# Mosfet_cct.net
KiCad netlist of a schematic drawn in Altium Designer
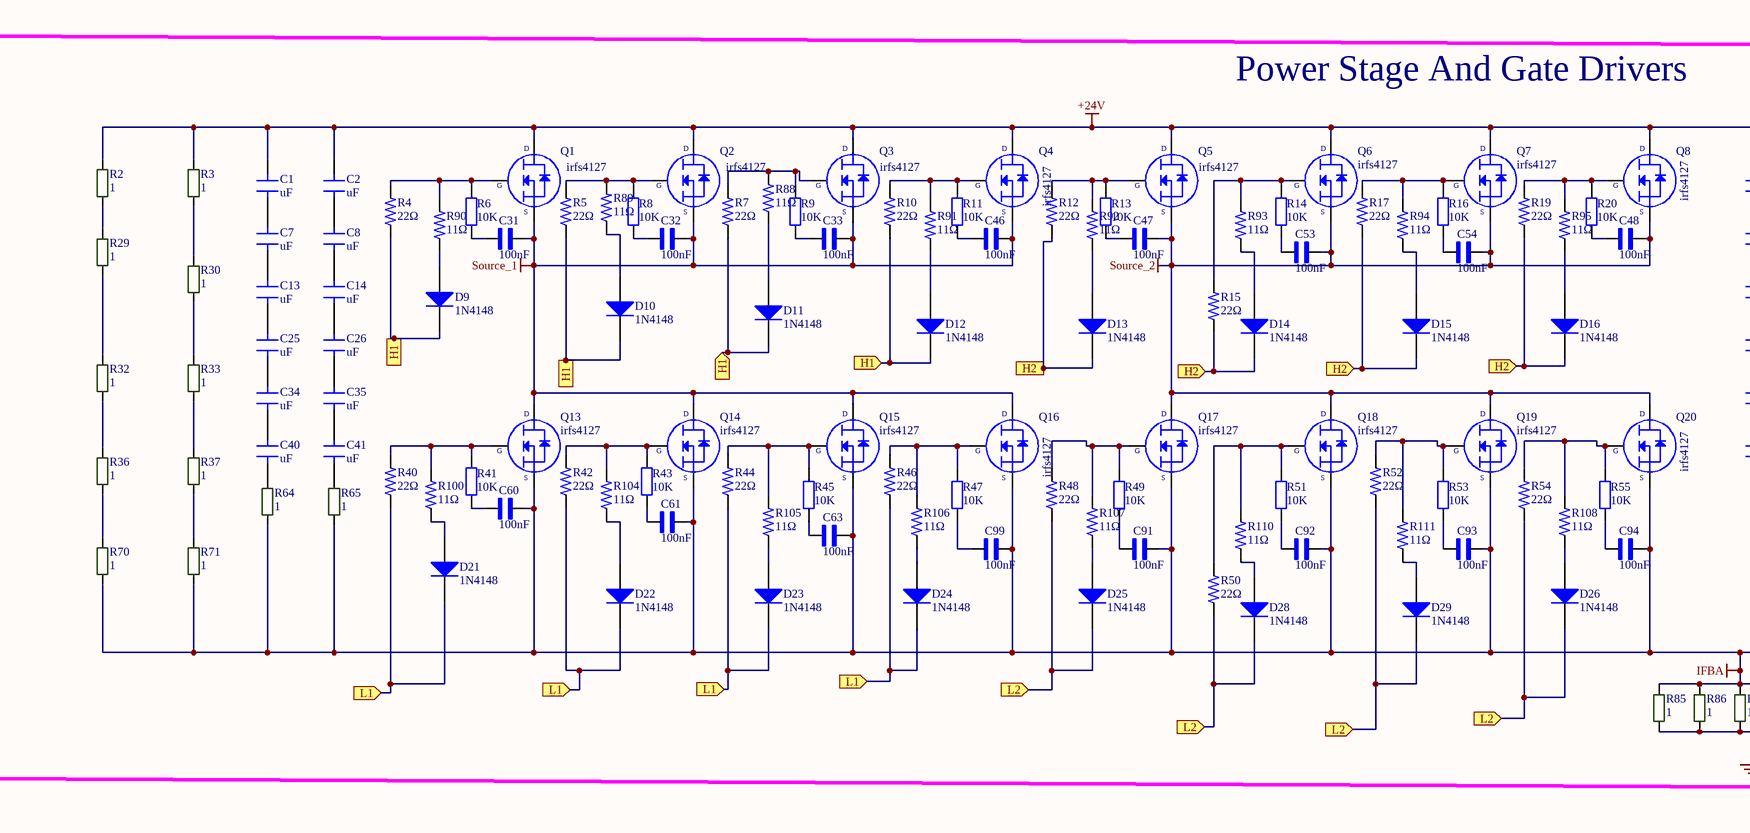
[diagram p0: Mosfet_cct.SchDoc, left]
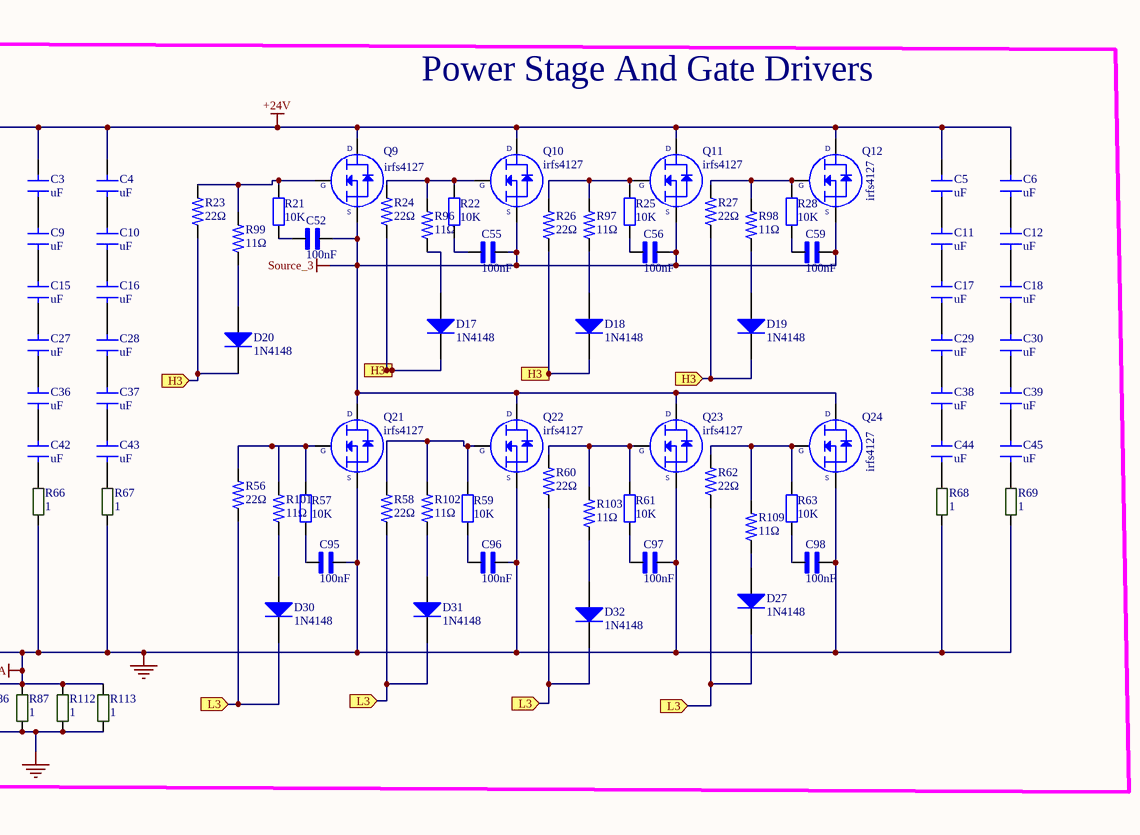
[diagram p1: Mosfet_cct.SchDoc, right]

(export (version "E")
  (design (tool "Eeschema 10.0.6"))
  (components
    (comp (ref "C1")
      (value "uF")
      (footprint "C-1206")
      (libsource (lib "LFI Power BoardSchlib1") (part "C-1206"))
    )
    (comp (ref "C2")
      (value "uF")
      (footprint "C-1206")
      (libsource (lib "LFI Power BoardSchlib1") (part "C-1206"))
    )
    (comp (ref "C3")
      (value "uF")
      (footprint "C-1206")
      (libsource (lib "LFI Power BoardSchlib1") (part "C-1206"))
    )
    (comp (ref "C4")
      (value "uF")
      (footprint "C-1206")
      (libsource (lib "LFI Power BoardSchlib1") (part "C-1206"))
    )
    (comp (ref "C5")
      (value "uF")
      (footprint "C-1206")
      (libsource (lib "LFI Power BoardSchlib1") (part "C-1206"))
    )
    (comp (ref "C6")
      (value "uF")
      (footprint "C-1206")
      (libsource (lib "LFI Power BoardSchlib1") (part "C-1206"))
    )
    (comp (ref "C7")
      (value "uF")
      (footprint "C-1206")
      (libsource (lib "LFI Power BoardSchlib1") (part "C-1206"))
    )
    (comp (ref "C8")
      (value "uF")
      (footprint "C-1206")
      (libsource (lib "LFI Power BoardSchlib1") (part "C-1206"))
    )
    (comp (ref "C9")
      (value "uF")
      (footprint "C-1206")
      (libsource (lib "LFI Power BoardSchlib1") (part "C-1206"))
    )
    (comp (ref "C10")
      (value "uF")
      (footprint "C-1206")
      (libsource (lib "LFI Power BoardSchlib1") (part "C-1206"))
    )
    (comp (ref "C11")
      (value "uF")
      (footprint "C-1206")
      (libsource (lib "LFI Power BoardSchlib1") (part "C-1206"))
    )
    (comp (ref "C12")
      (value "uF")
      (footprint "C-1206")
      (libsource (lib "LFI Power BoardSchlib1") (part "C-1206"))
    )
    (comp (ref "C13")
      (value "uF")
      (footprint "C-1206")
      (libsource (lib "LFI Power BoardSchlib1") (part "C-1206"))
    )
    (comp (ref "C14")
      (value "uF")
      (footprint "C-1206")
      (libsource (lib "LFI Power BoardSchlib1") (part "C-1206"))
    )
    (comp (ref "C15")
      (value "uF")
      (footprint "C-1206")
      (libsource (lib "LFI Power BoardSchlib1") (part "C-1206"))
    )
    (comp (ref "C16")
      (value "uF")
      (footprint "C-1206")
      (libsource (lib "LFI Power BoardSchlib1") (part "C-1206"))
    )
    (comp (ref "C17")
      (value "uF")
      (footprint "C-1206")
      (libsource (lib "LFI Power BoardSchlib1") (part "C-1206"))
    )
    (comp (ref "C18")
      (value "uF")
      (footprint "C-1206")
      (libsource (lib "LFI Power BoardSchlib1") (part "C-1206"))
    )
    (comp (ref "C25")
      (value "uF")
      (footprint "C-1206")
      (libsource (lib "LFI Power BoardSchlib1") (part "C-1206"))
    )
    (comp (ref "C26")
      (value "uF")
      (footprint "C-1206")
      (libsource (lib "LFI Power BoardSchlib1") (part "C-1206"))
    )
    (comp (ref "C27")
      (value "uF")
      (footprint "C-1206")
      (libsource (lib "LFI Power BoardSchlib1") (part "C-1206"))
    )
    (comp (ref "C28")
      (value "uF")
      (footprint "C-1206")
      (libsource (lib "LFI Power BoardSchlib1") (part "C-1206"))
    )
    (comp (ref "C29")
      (value "uF")
      (footprint "C-1206")
      (libsource (lib "LFI Power BoardSchlib1") (part "C-1206"))
    )
    (comp (ref "C30")
      (value "uF")
      (footprint "C-1206")
      (libsource (lib "LFI Power BoardSchlib1") (part "C-1206"))
    )
    (comp (ref "C31")
      (value "100nF")
      (footprint "C-0805W")
      (fields
        (field (name "MF") "Wurth Electronics Inc")
        (field (name "MP") "885012207098")
        (field (name "BUYPART") "https://www.snapeda.com/parts/885012207098/Wurth%20Electronics%20Inc/view-part/4217223/?ref=eda")
      )
      (libsource (lib "PROJE") (part "CAP 100nF 50V SMT 0805"))
    )
    (comp (ref "C32")
      (value "100nF")
      (footprint "C-0805W")
      (fields
        (field (name "MF") "Wurth Electronics Inc")
        (field (name "MP") "885012207098")
        (field (name "BUYPART") "https://www.snapeda.com/parts/885012207098/Wurth%20Electronics%20Inc/view-part/4217223/?ref=eda")
      )
      (libsource (lib "PROJE") (part "CAP 100nF 50V SMT 0805"))
    )
    (comp (ref "C33")
      (value "100nF")
      (footprint "C-0805W")
      (fields
        (field (name "MF") "Wurth Electronics Inc")
        (field (name "MP") "885012207098")
        (field (name "BUYPART") "https://www.snapeda.com/parts/885012207098/Wurth%20Electronics%20Inc/view-part/4217223/?ref=eda")
      )
      (libsource (lib "PROJE") (part "CAP 100nF 50V SMT 0805"))
    )
    (comp (ref "C34")
      (value "uF")
      (footprint "C-1206")
      (libsource (lib "LFI Power BoardSchlib1") (part "C-1206"))
    )
    (comp (ref "C35")
      (value "uF")
      (footprint "C-1206")
      (libsource (lib "LFI Power BoardSchlib1") (part "C-1206"))
    )
    (comp (ref "C36")
      (value "uF")
      (footprint "C-1206")
      (libsource (lib "LFI Power BoardSchlib1") (part "C-1206"))
    )
    (comp (ref "C37")
      (value "uF")
      (footprint "C-1206")
      (libsource (lib "LFI Power BoardSchlib1") (part "C-1206"))
    )
    (comp (ref "C38")
      (value "uF")
      (footprint "C-1206")
      (libsource (lib "LFI Power BoardSchlib1") (part "C-1206"))
    )
    (comp (ref "C39")
      (value "uF")
      (footprint "C-1206")
      (libsource (lib "LFI Power BoardSchlib1") (part "C-1206"))
    )
    (comp (ref "C40")
      (value "uF")
      (footprint "C-1206")
      (libsource (lib "LFI Power BoardSchlib1") (part "C-1206"))
    )
    (comp (ref "C41")
      (value "uF")
      (footprint "C-1206")
      (libsource (lib "LFI Power BoardSchlib1") (part "C-1206"))
    )
    (comp (ref "C42")
      (value "uF")
      (footprint "C-1206")
      (libsource (lib "LFI Power BoardSchlib1") (part "C-1206"))
    )
    (comp (ref "C43")
      (value "uF")
      (footprint "C-1206")
      (libsource (lib "LFI Power BoardSchlib1") (part "C-1206"))
    )
    (comp (ref "C44")
      (value "uF")
      (footprint "C-1206")
      (libsource (lib "LFI Power BoardSchlib1") (part "C-1206"))
    )
    (comp (ref "C45")
      (value "uF")
      (footprint "C-1206")
      (libsource (lib "LFI Power BoardSchlib1") (part "C-1206"))
    )
    (comp (ref "C46")
      (value "100nF")
      (footprint "C-0805W")
      (fields
        (field (name "MF") "Wurth Electronics Inc")
        (field (name "MP") "885012207098")
        (field (name "BUYPART") "https://www.snapeda.com/parts/885012207098/Wurth%20Electronics%20Inc/view-part/4217223/?ref=eda")
      )
      (libsource (lib "PROJE") (part "CAP 100nF 50V SMT 0805"))
    )
    (comp (ref "C47")
      (value "100nF")
      (footprint "C-0805W")
      (fields
        (field (name "MF") "Wurth Electronics Inc")
        (field (name "MP") "885012207098")
        (field (name "BUYPART") "https://www.snapeda.com/parts/885012207098/Wurth%20Electronics%20Inc/view-part/4217223/?ref=eda")
      )
      (libsource (lib "PROJE") (part "CAP 100nF 50V SMT 0805"))
    )
    (comp (ref "C48")
      (value "100nF")
      (footprint "C-0805W")
      (fields
        (field (name "MF") "Wurth Electronics Inc")
        (field (name "MP") "885012207098")
        (field (name "BUYPART") "https://www.snapeda.com/parts/885012207098/Wurth%20Electronics%20Inc/view-part/4217223/?ref=eda")
      )
      (libsource (lib "PROJE") (part "CAP 100nF 50V SMT 0805"))
    )
    (comp (ref "C52")
      (value "100nF")
      (footprint "C-0805W")
      (fields
        (field (name "MF") "Wurth Electronics Inc")
        (field (name "MP") "885012207098")
        (field (name "BUYPART") "https://www.snapeda.com/parts/885012207098/Wurth%20Electronics%20Inc/view-part/4217223/?ref=eda")
      )
      (libsource (lib "PROJE") (part "CAP 100nF 50V SMT 0805"))
    )
    (comp (ref "C53")
      (value "100nF")
      (footprint "C-0805W")
      (fields
        (field (name "MF") "Wurth Electronics Inc")
        (field (name "MP") "885012207098")
        (field (name "BUYPART") "https://www.snapeda.com/parts/885012207098/Wurth%20Electronics%20Inc/view-part/4217223/?ref=eda")
      )
      (libsource (lib "PROJE") (part "CAP 100nF 50V SMT 0805"))
    )
    (comp (ref "C54")
      (value "100nF")
      (footprint "C-0805W")
      (fields
        (field (name "MF") "Wurth Electronics Inc")
        (field (name "MP") "885012207098")
        (field (name "BUYPART") "https://www.snapeda.com/parts/885012207098/Wurth%20Electronics%20Inc/view-part/4217223/?ref=eda")
      )
      (libsource (lib "PROJE") (part "CAP 100nF 50V SMT 0805"))
    )
    (comp (ref "C55")
      (value "100nF")
      (footprint "C-0805W")
      (fields
        (field (name "MF") "Wurth Electronics Inc")
        (field (name "MP") "885012207098")
        (field (name "BUYPART") "https://www.snapeda.com/parts/885012207098/Wurth%20Electronics%20Inc/view-part/4217223/?ref=eda")
      )
      (libsource (lib "PROJE") (part "CAP 100nF 50V SMT 0805"))
    )
    (comp (ref "C56")
      (value "100nF")
      (footprint "C-0805W")
      (fields
        (field (name "MF") "Wurth Electronics Inc")
        (field (name "MP") "885012207098")
        (field (name "BUYPART") "https://www.snapeda.com/parts/885012207098/Wurth%20Electronics%20Inc/view-part/4217223/?ref=eda")
      )
      (libsource (lib "PROJE") (part "CAP 100nF 50V SMT 0805"))
    )
    (comp (ref "C59")
      (value "100nF")
      (footprint "C-0805W")
      (fields
        (field (name "MF") "Wurth Electronics Inc")
        (field (name "MP") "885012207098")
        (field (name "BUYPART") "https://www.snapeda.com/parts/885012207098/Wurth%20Electronics%20Inc/view-part/4217223/?ref=eda")
      )
      (libsource (lib "PROJE") (part "CAP 100nF 50V SMT 0805"))
    )
    (comp (ref "C60")
      (value "100nF")
      (footprint "C-0805W")
      (fields
        (field (name "MF") "Wurth Electronics Inc")
        (field (name "MP") "885012207098")
        (field (name "BUYPART") "https://www.snapeda.com/parts/885012207098/Wurth%20Electronics%20Inc/view-part/4217223/?ref=eda")
      )
      (libsource (lib "PROJE") (part "CAP 100nF 50V SMT 0805"))
    )
    (comp (ref "C61")
      (value "100nF")
      (footprint "C-0805W")
      (fields
        (field (name "MF") "Wurth Electronics Inc")
        (field (name "MP") "885012207098")
        (field (name "BUYPART") "https://www.snapeda.com/parts/885012207098/Wurth%20Electronics%20Inc/view-part/4217223/?ref=eda")
      )
      (libsource (lib "PROJE") (part "CAP 100nF 50V SMT 0805"))
    )
    (comp (ref "C63")
      (value "100nF")
      (footprint "C-0805W")
      (fields
        (field (name "MF") "Wurth Electronics Inc")
        (field (name "MP") "885012207098")
        (field (name "BUYPART") "https://www.snapeda.com/parts/885012207098/Wurth%20Electronics%20Inc/view-part/4217223/?ref=eda")
      )
      (libsource (lib "PROJE") (part "CAP 100nF 50V SMT 0805"))
    )
    (comp (ref "C91")
      (value "100nF")
      (footprint "C-0805W")
      (fields
        (field (name "MF") "Wurth Electronics Inc")
        (field (name "MP") "885012207098")
        (field (name "BUYPART") "https://www.snapeda.com/parts/885012207098/Wurth%20Electronics%20Inc/view-part/4217223/?ref=eda")
      )
      (libsource (lib "PROJE") (part "CAP 100nF 50V SMT 0805"))
    )
    (comp (ref "C92")
      (value "100nF")
      (footprint "C-0805W")
      (fields
        (field (name "MF") "Wurth Electronics Inc")
        (field (name "MP") "885012207098")
        (field (name "BUYPART") "https://www.snapeda.com/parts/885012207098/Wurth%20Electronics%20Inc/view-part/4217223/?ref=eda")
      )
      (libsource (lib "PROJE") (part "CAP 100nF 50V SMT 0805"))
    )
    (comp (ref "C93")
      (value "100nF")
      (footprint "C-0805W")
      (fields
        (field (name "MF") "Wurth Electronics Inc")
        (field (name "MP") "885012207098")
        (field (name "BUYPART") "https://www.snapeda.com/parts/885012207098/Wurth%20Electronics%20Inc/view-part/4217223/?ref=eda")
      )
      (libsource (lib "PROJE") (part "CAP 100nF 50V SMT 0805"))
    )
    (comp (ref "C94")
      (value "100nF")
      (footprint "C-0805W")
      (fields
        (field (name "MF") "Wurth Electronics Inc")
        (field (name "MP") "885012207098")
        (field (name "BUYPART") "https://www.snapeda.com/parts/885012207098/Wurth%20Electronics%20Inc/view-part/4217223/?ref=eda")
      )
      (libsource (lib "PROJE") (part "CAP 100nF 50V SMT 0805"))
    )
    (comp (ref "C95")
      (value "100nF")
      (footprint "C-0805W")
      (fields
        (field (name "MF") "Wurth Electronics Inc")
        (field (name "MP") "885012207098")
        (field (name "BUYPART") "https://www.snapeda.com/parts/885012207098/Wurth%20Electronics%20Inc/view-part/4217223/?ref=eda")
      )
      (libsource (lib "PROJE") (part "CAP 100nF 50V SMT 0805"))
    )
    (comp (ref "C96")
      (value "100nF")
      (footprint "C-0805W")
      (fields
        (field (name "MF") "Wurth Electronics Inc")
        (field (name "MP") "885012207098")
        (field (name "BUYPART") "https://www.snapeda.com/parts/885012207098/Wurth%20Electronics%20Inc/view-part/4217223/?ref=eda")
      )
      (libsource (lib "PROJE") (part "CAP 100nF 50V SMT 0805"))
    )
    (comp (ref "C97")
      (value "100nF")
      (footprint "C-0805W")
      (fields
        (field (name "MF") "Wurth Electronics Inc")
        (field (name "MP") "885012207098")
        (field (name "BUYPART") "https://www.snapeda.com/parts/885012207098/Wurth%20Electronics%20Inc/view-part/4217223/?ref=eda")
      )
      (libsource (lib "PROJE") (part "CAP 100nF 50V SMT 0805"))
    )
    (comp (ref "C98")
      (value "100nF")
      (footprint "C-0805W")
      (fields
        (field (name "MF") "Wurth Electronics Inc")
        (field (name "MP") "885012207098")
        (field (name "BUYPART") "https://www.snapeda.com/parts/885012207098/Wurth%20Electronics%20Inc/view-part/4217223/?ref=eda")
      )
      (libsource (lib "PROJE") (part "CAP 100nF 50V SMT 0805"))
    )
    (comp (ref "C99")
      (value "100nF")
      (footprint "C-0805W")
      (fields
        (field (name "MF") "Wurth Electronics Inc")
        (field (name "MP") "885012207098")
        (field (name "BUYPART") "https://www.snapeda.com/parts/885012207098/Wurth%20Electronics%20Inc/view-part/4217223/?ref=eda")
      )
      (libsource (lib "PROJE") (part "CAP 100nF 50V SMT 0805"))
    )
    (comp (ref "D9")
      (value "1N4148 Diyot")
      (footprint "SOD-123")
      (description "DIODE GEN PURP 100V 150MA SOD123")
      (fields (field (name "DEGER") "1N4148"))
      (libsource (lib "PROJE") (part "1N4148"))
    )
    (comp (ref "D10")
      (value "1N4148 Diyot")
      (footprint "SOD-123")
      (description "DIODE GEN PURP 100V 150MA SOD123")
      (fields (field (name "DEGER") "1N4148"))
      (libsource (lib "PROJE") (part "1N4148"))
    )
    (comp (ref "D11")
      (value "1N4148 Diyot")
      (footprint "SOD-123")
      (description "DIODE GEN PURP 100V 150MA SOD123")
      (fields (field (name "DEGER") "1N4148"))
      (libsource (lib "PROJE") (part "1N4148"))
    )
    (comp (ref "D12")
      (value "1N4148 Diyot")
      (footprint "SOD-123")
      (description "DIODE GEN PURP 100V 150MA SOD123")
      (fields (field (name "DEGER") "1N4148"))
      (libsource (lib "PROJE") (part "1N4148"))
    )
    (comp (ref "D13")
      (value "1N4148 Diyot")
      (footprint "SOD-123")
      (description "DIODE GEN PURP 100V 150MA SOD123")
      (fields (field (name "DEGER") "1N4148"))
      (libsource (lib "PROJE") (part "1N4148"))
    )
    (comp (ref "D14")
      (value "1N4148 Diyot")
      (footprint "SOD-123")
      (description "DIODE GEN PURP 100V 150MA SOD123")
      (fields (field (name "DEGER") "1N4148"))
      (libsource (lib "PROJE") (part "1N4148"))
    )
    (comp (ref "D15")
      (value "1N4148 Diyot")
      (footprint "SOD-123")
      (description "DIODE GEN PURP 100V 150MA SOD123")
      (fields (field (name "DEGER") "1N4148"))
      (libsource (lib "PROJE") (part "1N4148"))
    )
    (comp (ref "D16")
      (value "1N4148 Diyot")
      (footprint "SOD-123")
      (description "DIODE GEN PURP 100V 150MA SOD123")
      (fields (field (name "DEGER") "1N4148"))
      (libsource (lib "PROJE") (part "1N4148"))
    )
    (comp (ref "D17")
      (value "1N4148 Diyot")
      (footprint "SOD-123")
      (description "DIODE GEN PURP 100V 150MA SOD123")
      (fields (field (name "DEGER") "1N4148"))
      (libsource (lib "PROJE") (part "1N4148"))
    )
    (comp (ref "D18")
      (value "1N4148 Diyot")
      (footprint "SOD-123")
      (description "DIODE GEN PURP 100V 150MA SOD123")
      (fields (field (name "DEGER") "1N4148"))
      (libsource (lib "PROJE") (part "1N4148"))
    )
    (comp (ref "D19")
      (value "1N4148 Diyot")
      (footprint "SOD-123")
      (description "DIODE GEN PURP 100V 150MA SOD123")
      (fields (field (name "DEGER") "1N4148"))
      (libsource (lib "PROJE") (part "1N4148"))
    )
    (comp (ref "D20")
      (value "1N4148 Diyot")
      (footprint "SOD-123")
      (description "DIODE GEN PURP 100V 150MA SOD123")
      (fields (field (name "DEGER") "1N4148"))
      (libsource (lib "PROJE") (part "1N4148"))
    )
    (comp (ref "D21")
      (value "1N4148 Diyot")
      (footprint "SOD-123")
      (description "DIODE GEN PURP 100V 150MA SOD123")
      (fields (field (name "DEGER") "1N4148"))
      (libsource (lib "PROJE") (part "1N4148"))
    )
    (comp (ref "D22")
      (value "1N4148 Diyot")
      (footprint "SOD-123")
      (description "DIODE GEN PURP 100V 150MA SOD123")
      (fields (field (name "DEGER") "1N4148"))
      (libsource (lib "PROJE") (part "1N4148"))
    )
    (comp (ref "D23")
      (value "1N4148 Diyot")
      (footprint "SOD-123")
      (description "DIODE GEN PURP 100V 150MA SOD123")
      (fields (field (name "DEGER") "1N4148"))
      (libsource (lib "PROJE") (part "1N4148"))
    )
    (comp (ref "D24")
      (value "1N4148 Diyot")
      (footprint "SOD-123")
      (description "DIODE GEN PURP 100V 150MA SOD123")
      (fields (field (name "DEGER") "1N4148"))
      (libsource (lib "PROJE") (part "1N4148"))
    )
    (comp (ref "D25")
      (value "1N4148 Diyot")
      (footprint "SOD-123")
      (description "DIODE GEN PURP 100V 150MA SOD123")
      (fields (field (name "DEGER") "1N4148"))
      (libsource (lib "PROJE") (part "1N4148"))
    )
    (comp (ref "D26")
      (value "1N4148 Diyot")
      (footprint "SOD-123")
      (description "DIODE GEN PURP 100V 150MA SOD123")
      (fields (field (name "DEGER") "1N4148"))
      (libsource (lib "PROJE") (part "1N4148"))
    )
    (comp (ref "D27")
      (value "1N4148 Diyot")
      (footprint "SOD-123")
      (description "DIODE GEN PURP 100V 150MA SOD123")
      (fields (field (name "DEGER") "1N4148"))
      (libsource (lib "PROJE") (part "1N4148"))
    )
    (comp (ref "D28")
      (value "1N4148 Diyot")
      (footprint "SOD-123")
      (description "DIODE GEN PURP 100V 150MA SOD123")
      (fields (field (name "DEGER") "1N4148"))
      (libsource (lib "PROJE") (part "1N4148"))
    )
    (comp (ref "D29")
      (value "1N4148 Diyot")
      (footprint "SOD-123")
      (description "DIODE GEN PURP 100V 150MA SOD123")
      (fields (field (name "DEGER") "1N4148"))
      (libsource (lib "PROJE") (part "1N4148"))
    )
    (comp (ref "D30")
      (value "1N4148 Diyot")
      (footprint "SOD-123")
      (description "DIODE GEN PURP 100V 150MA SOD123")
      (fields (field (name "DEGER") "1N4148"))
      (libsource (lib "PROJE") (part "1N4148"))
    )
    (comp (ref "D31")
      (value "1N4148 Diyot")
      (footprint "SOD-123")
      (description "DIODE GEN PURP 100V 150MA SOD123")
      (fields (field (name "DEGER") "1N4148"))
      (libsource (lib "PROJE") (part "1N4148"))
    )
    (comp (ref "D32")
      (value "1N4148 Diyot")
      (footprint "SOD-123")
      (description "DIODE GEN PURP 100V 150MA SOD123")
      (fields (field (name "DEGER") "1N4148"))
      (libsource (lib "PROJE") (part "1N4148"))
    )
    (comp (ref "Q1")
      (value "irfs4127")
      (footprint "DPAK_TO263")
      (description "MOSFET N-CH 200V 72A D2PAK")
      (fields
        (field (name "MANUFACTURER") "International Rectifier")
        (field (name "MANUFACTURER PART NUMBER") "IRFS4127TRLPBF")
      )
      (libsource (lib "LFI Power BoardSchlib1") (part "IRFS4127TRLPBF"))
    )
    (comp (ref "Q2")
      (value "irfs4127")
      (footprint "DPAK_TO263")
      (description "MOSFET N-CH 200V 72A D2PAK")
      (fields
        (field (name "MANUFACTURER") "International Rectifier")
        (field (name "MANUFACTURER PART NUMBER") "IRFS4127TRLPBF")
      )
      (libsource (lib "LFI Power BoardSchlib1") (part "IRFS4127TRLPBF"))
    )
    (comp (ref "Q3")
      (value "irfs4127")
      (footprint "DPAK_TO263")
      (description "MOSFET N-CH 200V 72A D2PAK")
      (fields
        (field (name "MANUFACTURER") "International Rectifier")
        (field (name "MANUFACTURER PART NUMBER") "IRFS4127TRLPBF")
      )
      (libsource (lib "LFI Power BoardSchlib1") (part "IRFS4127TRLPBF"))
    )
    (comp (ref "Q4")
      (value "irfs4127")
      (footprint "DPAK_TO263")
      (description "MOSFET N-CH 200V 72A D2PAK")
      (fields
        (field (name "MANUFACTURER") "International Rectifier")
        (field (name "MANUFACTURER PART NUMBER") "IRFS4127TRLPBF")
      )
      (libsource (lib "LFI Power BoardSchlib1") (part "IRFS4127TRLPBF"))
    )
    (comp (ref "Q5")
      (value "irfs4127")
      (footprint "DPAK_TO263")
      (description "MOSFET N-CH 200V 72A D2PAK")
      (fields
        (field (name "MANUFACTURER") "International Rectifier")
        (field (name "MANUFACTURER PART NUMBER") "IRFS4127TRLPBF")
      )
      (libsource (lib "LFI Power BoardSchlib1") (part "IRFS4127TRLPBF"))
    )
    (comp (ref "Q6")
      (value "irfs4127")
      (footprint "DPAK_TO263")
      (description "MOSFET N-CH 200V 72A D2PAK")
      (fields
        (field (name "MANUFACTURER") "International Rectifier")
        (field (name "MANUFACTURER PART NUMBER") "IRFS4127TRLPBF")
      )
      (libsource (lib "LFI Power BoardSchlib1") (part "IRFS4127TRLPBF"))
    )
    (comp (ref "Q7")
      (value "irfs4127")
      (footprint "DPAK_TO263")
      (description "MOSFET N-CH 200V 72A D2PAK")
      (fields
        (field (name "MANUFACTURER") "International Rectifier")
        (field (name "MANUFACTURER PART NUMBER") "IRFS4127TRLPBF")
      )
      (libsource (lib "LFI Power BoardSchlib1") (part "IRFS4127TRLPBF"))
    )
    (comp (ref "Q8")
      (value "irfs4127")
      (footprint "DPAK_TO263")
      (description "MOSFET N-CH 200V 72A D2PAK")
      (fields
        (field (name "MANUFACTURER") "International Rectifier")
        (field (name "MANUFACTURER PART NUMBER") "IRFS4127TRLPBF")
      )
      (libsource (lib "LFI Power BoardSchlib1") (part "IRFS4127TRLPBF"))
    )
    (comp (ref "Q9")
      (value "irfs4127")
      (footprint "DPAK_TO263")
      (description "MOSFET N-CH 200V 72A D2PAK")
      (fields
        (field (name "MANUFACTURER") "International Rectifier")
        (field (name "MANUFACTURER PART NUMBER") "IRFS4127TRLPBF")
      )
      (libsource (lib "LFI Power BoardSchlib1") (part "IRFS4127TRLPBF"))
    )
    (comp (ref "Q10")
      (value "irfs4127")
      (footprint "DPAK_TO263")
      (description "MOSFET N-CH 200V 72A D2PAK")
      (fields
        (field (name "MANUFACTURER") "International Rectifier")
        (field (name "MANUFACTURER PART NUMBER") "IRFS4127TRLPBF")
      )
      (libsource (lib "LFI Power BoardSchlib1") (part "IRFS4127TRLPBF"))
    )
    (comp (ref "Q11")
      (value "irfs4127")
      (footprint "DPAK_TO263")
      (description "MOSFET N-CH 200V 72A D2PAK")
      (fields
        (field (name "MANUFACTURER") "International Rectifier")
        (field (name "MANUFACTURER PART NUMBER") "IRFS4127TRLPBF")
      )
      (libsource (lib "LFI Power BoardSchlib1") (part "IRFS4127TRLPBF"))
    )
    (comp (ref "Q12")
      (value "irfs4127")
      (footprint "DPAK_TO263")
      (description "MOSFET N-CH 200V 72A D2PAK")
      (fields
        (field (name "MANUFACTURER") "International Rectifier")
        (field (name "MANUFACTURER PART NUMBER") "IRFS4127TRLPBF")
      )
      (libsource (lib "LFI Power BoardSchlib1") (part "IRFS4127TRLPBF"))
    )
    (comp (ref "Q13")
      (value "irfs4127")
      (footprint "DPAK_TO263")
      (description "MOSFET N-CH 200V 72A D2PAK")
      (fields
        (field (name "MANUFACTURER") "International Rectifier")
        (field (name "MANUFACTURER PART NUMBER") "IRFS4127TRLPBF")
      )
      (libsource (lib "LFI Power BoardSchlib1") (part "IRFS4127TRLPBF"))
    )
    (comp (ref "Q14")
      (value "irfs4127")
      (footprint "DPAK_TO263")
      (description "MOSFET N-CH 200V 72A D2PAK")
      (fields
        (field (name "MANUFACTURER") "International Rectifier")
        (field (name "MANUFACTURER PART NUMBER") "IRFS4127TRLPBF")
      )
      (libsource (lib "LFI Power BoardSchlib1") (part "IRFS4127TRLPBF"))
    )
    (comp (ref "Q15")
      (value "irfs4127")
      (footprint "DPAK_TO263")
      (description "MOSFET N-CH 200V 72A D2PAK")
      (fields
        (field (name "MANUFACTURER") "International Rectifier")
        (field (name "MANUFACTURER PART NUMBER") "IRFS4127TRLPBF")
      )
      (libsource (lib "LFI Power BoardSchlib1") (part "IRFS4127TRLPBF"))
    )
    (comp (ref "Q16")
      (value "irfs4127")
      (footprint "DPAK_TO263")
      (description "MOSFET N-CH 200V 72A D2PAK")
      (fields
        (field (name "MANUFACTURER") "International Rectifier")
        (field (name "MANUFACTURER PART NUMBER") "IRFS4127TRLPBF")
      )
      (libsource (lib "LFI Power BoardSchlib1") (part "IRFS4127TRLPBF"))
    )
    (comp (ref "Q17")
      (value "irfs4127")
      (footprint "DPAK_TO263")
      (description "MOSFET N-CH 200V 72A D2PAK")
      (fields
        (field (name "MANUFACTURER") "International Rectifier")
        (field (name "MANUFACTURER PART NUMBER") "IRFS4127TRLPBF")
      )
      (libsource (lib "LFI Power BoardSchlib1") (part "IRFS4127TRLPBF"))
    )
    (comp (ref "Q18")
      (value "irfs4127")
      (footprint "DPAK_TO263")
      (description "MOSFET N-CH 200V 72A D2PAK")
      (fields
        (field (name "MANUFACTURER") "International Rectifier")
        (field (name "MANUFACTURER PART NUMBER") "IRFS4127TRLPBF")
      )
      (libsource (lib "LFI Power BoardSchlib1") (part "IRFS4127TRLPBF"))
    )
    (comp (ref "Q19")
      (value "irfs4127")
      (footprint "DPAK_TO263")
      (description "MOSFET N-CH 200V 72A D2PAK")
      (fields
        (field (name "MANUFACTURER") "International Rectifier")
        (field (name "MANUFACTURER PART NUMBER") "IRFS4127TRLPBF")
      )
      (libsource (lib "LFI Power BoardSchlib1") (part "IRFS4127TRLPBF"))
    )
    (comp (ref "Q20")
      (value "irfs4127")
      (footprint "DPAK_TO263")
      (description "MOSFET N-CH 200V 72A D2PAK")
      (fields
        (field (name "MANUFACTURER") "International Rectifier")
        (field (name "MANUFACTURER PART NUMBER") "IRFS4127TRLPBF")
      )
      (libsource (lib "LFI Power BoardSchlib1") (part "IRFS4127TRLPBF"))
    )
    (comp (ref "Q21")
      (value "irfs4127")
      (footprint "DPAK_TO263")
      (description "MOSFET N-CH 200V 72A D2PAK")
      (fields
        (field (name "MANUFACTURER") "International Rectifier")
        (field (name "MANUFACTURER PART NUMBER") "IRFS4127TRLPBF")
      )
      (libsource (lib "LFI Power BoardSchlib1") (part "IRFS4127TRLPBF"))
    )
    (comp (ref "Q22")
      (value "irfs4127")
      (footprint "DPAK_TO263")
      (description "MOSFET N-CH 200V 72A D2PAK")
      (fields
        (field (name "MANUFACTURER") "International Rectifier")
        (field (name "MANUFACTURER PART NUMBER") "IRFS4127TRLPBF")
      )
      (libsource (lib "LFI Power BoardSchlib1") (part "IRFS4127TRLPBF"))
    )
    (comp (ref "Q23")
      (value "irfs4127")
      (footprint "DPAK_TO263")
      (description "MOSFET N-CH 200V 72A D2PAK")
      (fields
        (field (name "MANUFACTURER") "International Rectifier")
        (field (name "MANUFACTURER PART NUMBER") "IRFS4127TRLPBF")
      )
      (libsource (lib "LFI Power BoardSchlib1") (part "IRFS4127TRLPBF"))
    )
    (comp (ref "Q24")
      (value "irfs4127")
      (footprint "DPAK_TO263")
      (description "MOSFET N-CH 200V 72A D2PAK")
      (fields
        (field (name "MANUFACTURER") "International Rectifier")
        (field (name "MANUFACTURER PART NUMBER") "IRFS4127TRLPBF")
      )
      (libsource (lib "LFI Power BoardSchlib1") (part "IRFS4127TRLPBF"))
    )
    (comp (ref "R2")
      (value "1")
      (footprint "R-2512W")
      (libsource (lib "LFI Power BoardSchlib1") (part "0207 melf"))
    )
    (comp (ref "R3")
      (value "1")
      (footprint "R-2512W")
      (libsource (lib "LFI Power BoardSchlib1") (part "0207 melf"))
    )
    (comp (ref "R4")
      (value "22Ω")
      (footprint "R-1206W")
      (description "CRG1206 1% 22R")
      (fields (field (name "MP") "1623463-1"))
      (libsource (lib "PROJE") (part "RES 22Ω 1206"))
    )
    (comp (ref "R5")
      (value "22Ω")
      (footprint "R-1206W")
      (description "CRG1206 1% 22R")
      (fields (field (name "MP") "1623463-1"))
      (libsource (lib "PROJE") (part "RES 22Ω 1206"))
    )
    (comp (ref "R6")
      (value "RES SMD 10K OHM 1% 1/8W 0805")
      (footprint "R-0805W")
      (description "10 kOhms ±1% 0.125W, 1/8W Chip Resistor 0805 (2012 Metric) Moisture Resistant Thick Film")
      (fields (field (name "DEGER") "10K"))
      (libsource (lib "PROJE") (part "10K 0805"))
    )
    (comp (ref "R7")
      (value "22Ω")
      (footprint "R-1206W")
      (description "CRG1206 1% 22R")
      (fields (field (name "MP") "1623463-1"))
      (libsource (lib "PROJE") (part "RES 22Ω 1206"))
    )
    (comp (ref "R8")
      (value "RES SMD 10K OHM 1% 1/8W 0805")
      (footprint "R-0805W")
      (description "10 kOhms ±1% 0.125W, 1/8W Chip Resistor 0805 (2012 Metric) Moisture Resistant Thick Film")
      (fields (field (name "DEGER") "10K"))
      (libsource (lib "PROJE") (part "10K 0805"))
    )
    (comp (ref "R9")
      (value "RES SMD 10K OHM 1% 1/8W 0805")
      (footprint "R-0805W")
      (description "10 kOhms ±1% 0.125W, 1/8W Chip Resistor 0805 (2012 Metric) Moisture Resistant Thick Film")
      (fields (field (name "DEGER") "10K"))
      (libsource (lib "PROJE") (part "10K 0805"))
    )
    (comp (ref "R10")
      (value "22Ω")
      (footprint "R-1206W")
      (description "CRG1206 1% 22R")
      (fields (field (name "MP") "1623463-1"))
      (libsource (lib "PROJE") (part "RES 22Ω 1206"))
    )
    (comp (ref "R11")
      (value "RES SMD 10K OHM 1% 1/8W 0805")
      (footprint "R-0805W")
      (description "10 kOhms ±1% 0.125W, 1/8W Chip Resistor 0805 (2012 Metric) Moisture Resistant Thick Film")
      (fields (field (name "DEGER") "10K"))
      (libsource (lib "PROJE") (part "10K 0805"))
    )
    (comp (ref "R12")
      (value "22Ω")
      (footprint "R-1206W")
      (description "CRG1206 1% 22R")
      (fields (field (name "MP") "1623463-1"))
      (libsource (lib "PROJE") (part "RES 22Ω 1206"))
    )
    (comp (ref "R13")
      (value "RES SMD 10K OHM 1% 1/8W 0805")
      (footprint "R-0805W")
      (description "10 kOhms ±1% 0.125W, 1/8W Chip Resistor 0805 (2012 Metric) Moisture Resistant Thick Film")
      (fields (field (name "DEGER") "10K"))
      (libsource (lib "PROJE") (part "10K 0805"))
    )
    (comp (ref "R14")
      (value "RES SMD 10K OHM 1% 1/8W 0805")
      (footprint "R-0805W")
      (description "10 kOhms ±1% 0.125W, 1/8W Chip Resistor 0805 (2012 Metric) Moisture Resistant Thick Film")
      (fields (field (name "DEGER") "10K"))
      (libsource (lib "PROJE") (part "10K 0805"))
    )
    (comp (ref "R15")
      (value "22Ω")
      (footprint "R-1206W")
      (description "CRG1206 1% 22R")
      (fields (field (name "MP") "1623463-1"))
      (libsource (lib "PROJE") (part "RES 22Ω 1206"))
    )
    (comp (ref "R16")
      (value "RES SMD 10K OHM 1% 1/8W 0805")
      (footprint "R-0805W")
      (description "10 kOhms ±1% 0.125W, 1/8W Chip Resistor 0805 (2012 Metric) Moisture Resistant Thick Film")
      (fields (field (name "DEGER") "10K"))
      (libsource (lib "PROJE") (part "10K 0805"))
    )
    (comp (ref "R17")
      (value "22Ω")
      (footprint "R-1206W")
      (description "CRG1206 1% 22R")
      (fields (field (name "MP") "1623463-1"))
      (libsource (lib "PROJE") (part "RES 22Ω 1206"))
    )
    (comp (ref "R19")
      (value "22Ω")
      (footprint "R-1206W")
      (description "CRG1206 1% 22R")
      (fields (field (name "MP") "1623463-1"))
      (libsource (lib "PROJE") (part "RES 22Ω 1206"))
    )
    (comp (ref "R20")
      (value "RES SMD 10K OHM 1% 1/8W 0805")
      (footprint "R-0805W")
      (description "10 kOhms ±1% 0.125W, 1/8W Chip Resistor 0805 (2012 Metric) Moisture Resistant Thick Film")
      (fields (field (name "DEGER") "10K"))
      (libsource (lib "PROJE") (part "10K 0805"))
    )
    (comp (ref "R21")
      (value "RES SMD 10K OHM 1% 1/8W 0805")
      (footprint "R-0805W")
      (description "10 kOhms ±1% 0.125W, 1/8W Chip Resistor 0805 (2012 Metric) Moisture Resistant Thick Film")
      (fields (field (name "DEGER") "10K"))
      (libsource (lib "PROJE") (part "10K 0805"))
    )
    (comp (ref "R22")
      (value "RES SMD 10K OHM 1% 1/8W 0805")
      (footprint "R-0805W")
      (description "10 kOhms ±1% 0.125W, 1/8W Chip Resistor 0805 (2012 Metric) Moisture Resistant Thick Film")
      (fields (field (name "DEGER") "10K"))
      (libsource (lib "PROJE") (part "10K 0805"))
    )
    (comp (ref "R23")
      (value "22Ω")
      (footprint "R-1206W")
      (description "CRG1206 1% 22R")
      (fields (field (name "MP") "1623463-1"))
      (libsource (lib "PROJE") (part "RES 22Ω 1206"))
    )
    (comp (ref "R24")
      (value "22Ω")
      (footprint "R-1206W")
      (description "CRG1206 1% 22R")
      (fields (field (name "MP") "1623463-1"))
      (libsource (lib "PROJE") (part "RES 22Ω 1206"))
    )
    (comp (ref "R25")
      (value "RES SMD 10K OHM 1% 1/8W 0805")
      (footprint "R-0805W")
      (description "10 kOhms ±1% 0.125W, 1/8W Chip Resistor 0805 (2012 Metric) Moisture Resistant Thick Film")
      (fields (field (name "DEGER") "10K"))
      (libsource (lib "PROJE") (part "10K 0805"))
    )
    (comp (ref "R26")
      (value "22Ω")
      (footprint "R-1206W")
      (description "CRG1206 1% 22R")
      (fields (field (name "MP") "1623463-1"))
      (libsource (lib "PROJE") (part "RES 22Ω 1206"))
    )
    (comp (ref "R27")
      (value "22Ω")
      (footprint "R-1206W")
      (description "CRG1206 1% 22R")
      (fields (field (name "MP") "1623463-1"))
      (libsource (lib "PROJE") (part "RES 22Ω 1206"))
    )
    (comp (ref "R28")
      (value "RES SMD 10K OHM 1% 1/8W 0805")
      (footprint "R-0805W")
      (description "10 kOhms ±1% 0.125W, 1/8W Chip Resistor 0805 (2012 Metric) Moisture Resistant Thick Film")
      (fields (field (name "DEGER") "10K"))
      (libsource (lib "PROJE") (part "10K 0805"))
    )
    (comp (ref "R29")
      (value "1")
      (footprint "R-2512W")
      (libsource (lib "LFI Power BoardSchlib1") (part "0207 melf"))
    )
    (comp (ref "R30")
      (value "1")
      (footprint "R-2512W")
      (libsource (lib "LFI Power BoardSchlib1") (part "0207 melf"))
    )
    (comp (ref "R32")
      (value "1")
      (footprint "R-2512W")
      (libsource (lib "LFI Power BoardSchlib1") (part "0207 melf"))
    )
    (comp (ref "R33")
      (value "1")
      (footprint "R-2512W")
      (libsource (lib "LFI Power BoardSchlib1") (part "0207 melf"))
    )
    (comp (ref "R36")
      (value "1")
      (footprint "R-2512W")
      (libsource (lib "LFI Power BoardSchlib1") (part "0207 melf"))
    )
    (comp (ref "R37")
      (value "1")
      (footprint "R-2512W")
      (libsource (lib "LFI Power BoardSchlib1") (part "0207 melf"))
    )
    (comp (ref "R40")
      (value "22Ω")
      (footprint "R-1206W")
      (description "CRG1206 1% 22R")
      (fields (field (name "MP") "1623463-1"))
      (libsource (lib "PROJE") (part "RES 22Ω 1206"))
    )
    (comp (ref "R41")
      (value "RES SMD 10K OHM 1% 1/8W 0805")
      (footprint "R-0805W")
      (description "10 kOhms ±1% 0.125W, 1/8W Chip Resistor 0805 (2012 Metric) Moisture Resistant Thick Film")
      (fields (field (name "DEGER") "10K"))
      (libsource (lib "PROJE") (part "10K 0805"))
    )
    (comp (ref "R42")
      (value "22Ω")
      (footprint "R-1206W")
      (description "CRG1206 1% 22R")
      (fields (field (name "MP") "1623463-1"))
      (libsource (lib "PROJE") (part "RES 22Ω 1206"))
    )
    (comp (ref "R43")
      (value "RES SMD 10K OHM 1% 1/8W 0805")
      (footprint "R-0805W")
      (description "10 kOhms ±1% 0.125W, 1/8W Chip Resistor 0805 (2012 Metric) Moisture Resistant Thick Film")
      (fields (field (name "DEGER") "10K"))
      (libsource (lib "PROJE") (part "10K 0805"))
    )
    (comp (ref "R44")
      (value "22Ω")
      (footprint "R-1206W")
      (description "CRG1206 1% 22R")
      (fields (field (name "MP") "1623463-1"))
      (libsource (lib "PROJE") (part "RES 22Ω 1206"))
    )
    (comp (ref "R45")
      (value "RES SMD 10K OHM 1% 1/8W 0805")
      (footprint "R-0805W")
      (description "10 kOhms ±1% 0.125W, 1/8W Chip Resistor 0805 (2012 Metric) Moisture Resistant Thick Film")
      (fields (field (name "DEGER") "10K"))
      (libsource (lib "PROJE") (part "10K 0805"))
    )
    (comp (ref "R46")
      (value "22Ω")
      (footprint "R-1206W")
      (description "CRG1206 1% 22R")
      (fields (field (name "MP") "1623463-1"))
      (libsource (lib "PROJE") (part "RES 22Ω 1206"))
    )
    (comp (ref "R47")
      (value "RES SMD 10K OHM 1% 1/8W 0805")
      (footprint "R-0805W")
      (description "10 kOhms ±1% 0.125W, 1/8W Chip Resistor 0805 (2012 Metric) Moisture Resistant Thick Film")
      (fields (field (name "DEGER") "10K"))
      (libsource (lib "PROJE") (part "10K 0805"))
    )
    (comp (ref "R48")
      (value "22Ω")
      (footprint "R-1206W")
      (description "CRG1206 1% 22R")
      (fields (field (name "MP") "1623463-1"))
      (libsource (lib "PROJE") (part "RES 22Ω 1206"))
    )
    (comp (ref "R49")
      (value "RES SMD 10K OHM 1% 1/8W 0805")
      (footprint "R-0805W")
      (description "10 kOhms ±1% 0.125W, 1/8W Chip Resistor 0805 (2012 Metric) Moisture Resistant Thick Film")
      (fields (field (name "DEGER") "10K"))
      (libsource (lib "PROJE") (part "10K 0805"))
    )
    (comp (ref "R50")
      (value "22Ω")
      (footprint "R-1206W")
      (description "CRG1206 1% 22R")
      (fields (field (name "MP") "1623463-1"))
      (libsource (lib "PROJE") (part "RES 22Ω 1206"))
    )
    (comp (ref "R51")
      (value "RES SMD 10K OHM 1% 1/8W 0805")
      (footprint "R-0805W")
      (description "10 kOhms ±1% 0.125W, 1/8W Chip Resistor 0805 (2012 Metric) Moisture Resistant Thick Film")
      (fields (field (name "DEGER") "10K"))
      (libsource (lib "PROJE") (part "10K 0805"))
    )
    (comp (ref "R52")
      (value "22Ω")
      (footprint "R-1206W")
      (description "CRG1206 1% 22R")
      (fields (field (name "MP") "1623463-1"))
      (libsource (lib "PROJE") (part "RES 22Ω 1206"))
    )
    (comp (ref "R53")
      (value "RES SMD 10K OHM 1% 1/8W 0805")
      (footprint "R-0805W")
      (description "10 kOhms ±1% 0.125W, 1/8W Chip Resistor 0805 (2012 Metric) Moisture Resistant Thick Film")
      (fields (field (name "DEGER") "10K"))
      (libsource (lib "PROJE") (part "10K 0805"))
    )
    (comp (ref "R54")
      (value "22Ω")
      (footprint "R-1206W")
      (description "CRG1206 1% 22R")
      (fields (field (name "MP") "1623463-1"))
      (libsource (lib "PROJE") (part "RES 22Ω 1206"))
    )
    (comp (ref "R55")
      (value "RES SMD 10K OHM 1% 1/8W 0805")
      (footprint "R-0805W")
      (description "10 kOhms ±1% 0.125W, 1/8W Chip Resistor 0805 (2012 Metric) Moisture Resistant Thick Film")
      (fields (field (name "DEGER") "10K"))
      (libsource (lib "PROJE") (part "10K 0805"))
    )
    (comp (ref "R56")
      (value "22Ω")
      (footprint "R-1206W")
      (description "CRG1206 1% 22R")
      (fields (field (name "MP") "1623463-1"))
      (libsource (lib "PROJE") (part "RES 22Ω 1206"))
    )
    (comp (ref "R57")
      (value "RES SMD 10K OHM 1% 1/8W 0805")
      (footprint "R-0805W")
      (description "10 kOhms ±1% 0.125W, 1/8W Chip Resistor 0805 (2012 Metric) Moisture Resistant Thick Film")
      (fields (field (name "DEGER") "10K"))
      (libsource (lib "PROJE") (part "10K 0805"))
    )
    (comp (ref "R58")
      (value "22Ω")
      (footprint "R-1206W")
      (description "CRG1206 1% 22R")
      (fields (field (name "MP") "1623463-1"))
      (libsource (lib "PROJE") (part "RES 22Ω 1206"))
    )
    (comp (ref "R59")
      (value "RES SMD 10K OHM 1% 1/8W 0805")
      (footprint "R-0805W")
      (description "10 kOhms ±1% 0.125W, 1/8W Chip Resistor 0805 (2012 Metric) Moisture Resistant Thick Film")
      (fields (field (name "DEGER") "10K"))
      (libsource (lib "PROJE") (part "10K 0805"))
    )
    (comp (ref "R60")
      (value "22Ω")
      (footprint "R-1206W")
      (description "CRG1206 1% 22R")
      (fields (field (name "MP") "1623463-1"))
      (libsource (lib "PROJE") (part "RES 22Ω 1206"))
    )
    (comp (ref "R61")
      (value "RES SMD 10K OHM 1% 1/8W 0805")
      (footprint "R-0805W")
      (description "10 kOhms ±1% 0.125W, 1/8W Chip Resistor 0805 (2012 Metric) Moisture Resistant Thick Film")
      (fields (field (name "DEGER") "10K"))
      (libsource (lib "PROJE") (part "10K 0805"))
    )
    (comp (ref "R62")
      (value "22Ω")
      (footprint "R-1206W")
      (description "CRG1206 1% 22R")
      (fields (field (name "MP") "1623463-1"))
      (libsource (lib "PROJE") (part "RES 22Ω 1206"))
    )
    (comp (ref "R63")
      (value "RES SMD 10K OHM 1% 1/8W 0805")
      (footprint "R-0805W")
      (description "10 kOhms ±1% 0.125W, 1/8W Chip Resistor 0805 (2012 Metric) Moisture Resistant Thick Film")
      (fields (field (name "DEGER") "10K"))
      (libsource (lib "PROJE") (part "10K 0805"))
    )
    (comp (ref "R64")
      (value "1")
      (footprint "R-2512W")
      (libsource (lib "LFI Power BoardSchlib1") (part "0207 melf"))
    )
    (comp (ref "R65")
      (value "1")
      (footprint "R-2512W")
      (libsource (lib "LFI Power BoardSchlib1") (part "0207 melf"))
    )
    (comp (ref "R66")
      (value "1")
      (footprint "R-2512W")
      (libsource (lib "LFI Power BoardSchlib1") (part "0207 melf"))
    )
    (comp (ref "R67")
      (value "1")
      (footprint "R-2512W")
      (libsource (lib "LFI Power BoardSchlib1") (part "0207 melf"))
    )
    (comp (ref "R68")
      (value "1")
      (footprint "R-2512W")
      (libsource (lib "LFI Power BoardSchlib1") (part "0207 melf"))
    )
    (comp (ref "R69")
      (value "1")
      (footprint "R-2512W")
      (libsource (lib "LFI Power BoardSchlib1") (part "0207 melf"))
    )
    (comp (ref "R70")
      (value "1")
      (footprint "R-2512W")
      (libsource (lib "LFI Power BoardSchlib1") (part "0207 melf"))
    )
    (comp (ref "R71")
      (value "1")
      (footprint "R-2512W")
      (libsource (lib "LFI Power BoardSchlib1") (part "0207 melf"))
    )
    (comp (ref "R85")
      (value "1")
      (footprint "R-2512W")
      (libsource (lib "LFI Power BoardSchlib1") (part "0207 melf"))
    )
    (comp (ref "R86")
      (value "1")
      (footprint "R-2512W")
      (libsource (lib "LFI Power BoardSchlib1") (part "0207 melf"))
    )
    (comp (ref "R87")
      (value "1")
      (footprint "R-2512W")
      (libsource (lib "LFI Power BoardSchlib1") (part "0207 melf"))
    )
    (comp (ref "R88")
      (value "11Ω")
      (footprint "R-1206W")
      (description "CRG1206 1% 11R")
      (fields (field (name "MP") "1623463-1"))
      (libsource (lib "PROJE") (part "RES 11Ω 1206"))
    )
    (comp (ref "R89")
      (value "11Ω")
      (footprint "R-1206W")
      (description "CRG1206 1% 11R")
      (fields (field (name "MP") "1623463-1"))
      (libsource (lib "PROJE") (part "RES 11Ω 1206"))
    )
    (comp (ref "R90")
      (value "11Ω")
      (footprint "R-1206W")
      (description "CRG1206 1% 11R")
      (fields (field (name "MP") "1623463-1"))
      (libsource (lib "PROJE") (part "RES 11Ω 1206"))
    )
    (comp (ref "R91")
      (value "11Ω")
      (footprint "R-1206W")
      (description "CRG1206 1% 11R")
      (fields (field (name "MP") "1623463-1"))
      (libsource (lib "PROJE") (part "RES 11Ω 1206"))
    )
    (comp (ref "R92")
      (value "11Ω")
      (footprint "R-1206W")
      (description "CRG1206 1% 11R")
      (fields (field (name "MP") "1623463-1"))
      (libsource (lib "PROJE") (part "RES 11Ω 1206"))
    )
    (comp (ref "R93")
      (value "11Ω")
      (footprint "R-1206W")
      (description "CRG1206 1% 11R")
      (fields (field (name "MP") "1623463-1"))
      (libsource (lib "PROJE") (part "RES 11Ω 1206"))
    )
    (comp (ref "R94")
      (value "11Ω")
      (footprint "R-1206W")
      (description "CRG1206 1% 11R")
      (fields (field (name "MP") "1623463-1"))
      (libsource (lib "PROJE") (part "RES 11Ω 1206"))
    )
    (comp (ref "R95")
      (value "11Ω")
      (footprint "R-1206W")
      (description "CRG1206 1% 11R")
      (fields (field (name "MP") "1623463-1"))
      (libsource (lib "PROJE") (part "RES 11Ω 1206"))
    )
    (comp (ref "R96")
      (value "11Ω")
      (footprint "R-1206W")
      (description "CRG1206 1% 11R")
      (fields (field (name "MP") "1623463-1"))
      (libsource (lib "PROJE") (part "RES 11Ω 1206"))
    )
    (comp (ref "R97")
      (value "11Ω")
      (footprint "R-1206W")
      (description "CRG1206 1% 11R")
      (fields (field (name "MP") "1623463-1"))
      (libsource (lib "PROJE") (part "RES 11Ω 1206"))
    )
    (comp (ref "R98")
      (value "11Ω")
      (footprint "R-1206W")
      (description "CRG1206 1% 11R")
      (fields (field (name "MP") "1623463-1"))
      (libsource (lib "PROJE") (part "RES 11Ω 1206"))
    )
    (comp (ref "R99")
      (value "11Ω")
      (footprint "R-1206W")
      (description "CRG1206 1% 11R")
      (fields (field (name "MP") "1623463-1"))
      (libsource (lib "PROJE") (part "RES 11Ω 1206"))
    )
    (comp (ref "R100")
      (value "11Ω")
      (footprint "R-1206W")
      (description "CRG1206 1% 11R")
      (fields (field (name "MP") "1623463-1"))
      (libsource (lib "PROJE") (part "RES 11Ω 1206"))
    )
    (comp (ref "R101")
      (value "11Ω")
      (footprint "R-1206W")
      (description "CRG1206 1% 11R")
      (fields (field (name "MP") "1623463-1"))
      (libsource (lib "PROJE") (part "RES 11Ω 1206"))
    )
    (comp (ref "R102")
      (value "11Ω")
      (footprint "R-1206W")
      (description "CRG1206 1% 11R")
      (fields (field (name "MP") "1623463-1"))
      (libsource (lib "PROJE") (part "RES 11Ω 1206"))
    )
    (comp (ref "R103")
      (value "11Ω")
      (footprint "R-1206W")
      (description "CRG1206 1% 11R")
      (fields (field (name "MP") "1623463-1"))
      (libsource (lib "PROJE") (part "RES 11Ω 1206"))
    )
    (comp (ref "R104")
      (value "11Ω")
      (footprint "R-1206W")
      (description "CRG1206 1% 11R")
      (fields (field (name "MP") "1623463-1"))
      (libsource (lib "PROJE") (part "RES 11Ω 1206"))
    )
    (comp (ref "R105")
      (value "11Ω")
      (footprint "R-1206W")
      (description "CRG1206 1% 11R")
      (fields (field (name "MP") "1623463-1"))
      (libsource (lib "PROJE") (part "RES 11Ω 1206"))
    )
    (comp (ref "R106")
      (value "11Ω")
      (footprint "R-1206W")
      (description "CRG1206 1% 11R")
      (fields (field (name "MP") "1623463-1"))
      (libsource (lib "PROJE") (part "RES 11Ω 1206"))
    )
    (comp (ref "R107")
      (value "11Ω")
      (footprint "R-1206W")
      (description "CRG1206 1% 11R")
      (fields (field (name "MP") "1623463-1"))
      (libsource (lib "PROJE") (part "RES 11Ω 1206"))
    )
    (comp (ref "R108")
      (value "11Ω")
      (footprint "R-1206W")
      (description "CRG1206 1% 11R")
      (fields (field (name "MP") "1623463-1"))
      (libsource (lib "PROJE") (part "RES 11Ω 1206"))
    )
    (comp (ref "R109")
      (value "11Ω")
      (footprint "R-1206W")
      (description "CRG1206 1% 11R")
      (fields (field (name "MP") "1623463-1"))
      (libsource (lib "PROJE") (part "RES 11Ω 1206"))
    )
    (comp (ref "R110")
      (value "11Ω")
      (footprint "R-1206W")
      (description "CRG1206 1% 11R")
      (fields (field (name "MP") "1623463-1"))
      (libsource (lib "PROJE") (part "RES 11Ω 1206"))
    )
    (comp (ref "R111")
      (value "11Ω")
      (footprint "R-1206W")
      (description "CRG1206 1% 11R")
      (fields (field (name "MP") "1623463-1"))
      (libsource (lib "PROJE") (part "RES 11Ω 1206"))
    )
    (comp (ref "R112")
      (value "1")
      (footprint "R-2512W")
      (libsource (lib "LFI Power BoardSchlib1") (part "0207 melf"))
    )
    (comp (ref "R113")
      (value "1")
      (footprint "R-2512W")
      (libsource (lib "LFI Power BoardSchlib1") (part "0207 melf"))
    )
  )
  (nets
    (net (code "1") (name "+24V") (class "Default")
      (node (ref "C1") (pin "2") (pinfunction "2_2") (pintype "passive"))
      (node (ref "C2") (pin "2") (pinfunction "2_2") (pintype "passive"))
      (node (ref "C3") (pin "2") (pinfunction "2_2") (pintype "passive"))
      (node (ref "C4") (pin "2") (pinfunction "2_2") (pintype "passive"))
      (node (ref "C5") (pin "2") (pinfunction "2_2") (pintype "passive"))
      (node (ref "C6") (pin "2") (pinfunction "2_2") (pintype "passive"))
      (node (ref "Q1") (pin "3") (pinfunction "3_3") (pintype "passive"))
      (node (ref "Q10") (pin "3") (pinfunction "3_3") (pintype "passive"))
      (node (ref "Q11") (pin "3") (pinfunction "3_3") (pintype "passive"))
      (node (ref "Q12") (pin "3") (pinfunction "3_3") (pintype "passive"))
      (node (ref "Q2") (pin "3") (pinfunction "3_3") (pintype "passive"))
      (node (ref "Q3") (pin "3") (pinfunction "3_3") (pintype "passive"))
      (node (ref "Q4") (pin "3") (pinfunction "3_3") (pintype "passive"))
      (node (ref "Q5") (pin "3") (pinfunction "3_3") (pintype "passive"))
      (node (ref "Q6") (pin "3") (pinfunction "3_3") (pintype "passive"))
      (node (ref "Q7") (pin "3") (pinfunction "3_3") (pintype "passive"))
      (node (ref "Q8") (pin "3") (pinfunction "3_3") (pintype "passive"))
      (node (ref "Q9") (pin "3") (pinfunction "3_3") (pintype "passive"))
      (node (ref "R2") (pin "2") (pinfunction "2_2") (pintype "passive"))
      (node (ref "R3") (pin "2") (pinfunction "2_2") (pintype "passive"))
    )
    (net (code "2") (name "/H1") (class "Default")
      (node (ref "D10") (pin "2") (pinfunction "K_2") (pintype "passive"))
      (node (ref "D11") (pin "2") (pinfunction "K_2") (pintype "passive"))
      (node (ref "D12") (pin "2") (pinfunction "K_2") (pintype "passive"))
      (node (ref "D9") (pin "2") (pinfunction "K_2") (pintype "passive"))
      (node (ref "R10") (pin "1") (pinfunction "1_1") (pintype "passive"))
      (node (ref "R4") (pin "1") (pinfunction "1_1") (pintype "passive"))
      (node (ref "R5") (pin "1") (pinfunction "1_1") (pintype "passive"))
      (node (ref "R7") (pin "1") (pinfunction "1_1") (pintype "passive"))
    )
    (net (code "3") (name "/H2") (class "Default")
      (node (ref "D13") (pin "2") (pinfunction "K_2") (pintype "passive"))
      (node (ref "D14") (pin "2") (pinfunction "K_2") (pintype "passive"))
      (node (ref "D15") (pin "2") (pinfunction "K_2") (pintype "passive"))
      (node (ref "D16") (pin "2") (pinfunction "K_2") (pintype "passive"))
      (node (ref "R12") (pin "1") (pinfunction "1_1") (pintype "passive"))
      (node (ref "R15") (pin "1") (pinfunction "1_1") (pintype "passive"))
      (node (ref "R17") (pin "1") (pinfunction "1_1") (pintype "passive"))
      (node (ref "R19") (pin "1") (pinfunction "1_1") (pintype "passive"))
    )
    (net (code "4") (name "/H3") (class "Default")
      (node (ref "D17") (pin "2") (pinfunction "K_2") (pintype "passive"))
      (node (ref "D18") (pin "2") (pinfunction "K_2") (pintype "passive"))
      (node (ref "D19") (pin "2") (pinfunction "K_2") (pintype "passive"))
      (node (ref "D20") (pin "2") (pinfunction "K_2") (pintype "passive"))
      (node (ref "R23") (pin "1") (pinfunction "1_1") (pintype "passive"))
      (node (ref "R24") (pin "1") (pinfunction "1_1") (pintype "passive"))
      (node (ref "R26") (pin "1") (pinfunction "1_1") (pintype "passive"))
      (node (ref "R27") (pin "1") (pinfunction "1_1") (pintype "passive"))
    )
    (net (code "5") (name "/L1") (class "Default")
      (node (ref "D21") (pin "2") (pinfunction "K_2") (pintype "passive"))
      (node (ref "D22") (pin "2") (pinfunction "K_2") (pintype "passive"))
      (node (ref "D23") (pin "2") (pinfunction "K_2") (pintype "passive"))
      (node (ref "D24") (pin "2") (pinfunction "K_2") (pintype "passive"))
      (node (ref "R40") (pin "1") (pinfunction "1_1") (pintype "passive"))
      (node (ref "R42") (pin "1") (pinfunction "1_1") (pintype "passive"))
      (node (ref "R44") (pin "1") (pinfunction "1_1") (pintype "passive"))
      (node (ref "R46") (pin "1") (pinfunction "1_1") (pintype "passive"))
    )
    (net (code "6") (name "/L2") (class "Default")
      (node (ref "D25") (pin "2") (pinfunction "K_2") (pintype "passive"))
      (node (ref "D26") (pin "2") (pinfunction "K_2") (pintype "passive"))
      (node (ref "D28") (pin "2") (pinfunction "K_2") (pintype "passive"))
      (node (ref "D29") (pin "2") (pinfunction "K_2") (pintype "passive"))
      (node (ref "R48") (pin "1") (pinfunction "1_1") (pintype "passive"))
      (node (ref "R50") (pin "1") (pinfunction "1_1") (pintype "passive"))
      (node (ref "R52") (pin "1") (pinfunction "1_1") (pintype "passive"))
      (node (ref "R54") (pin "1") (pinfunction "1_1") (pintype "passive"))
    )
    (net (code "7") (name "/L3") (class "Default")
      (node (ref "D27") (pin "2") (pinfunction "K_2") (pintype "passive"))
      (node (ref "D30") (pin "2") (pinfunction "K_2") (pintype "passive"))
      (node (ref "D31") (pin "2") (pinfunction "K_2") (pintype "passive"))
      (node (ref "D32") (pin "2") (pinfunction "K_2") (pintype "passive"))
      (node (ref "R56") (pin "1") (pinfunction "1_1") (pintype "passive"))
      (node (ref "R58") (pin "1") (pinfunction "1_1") (pintype "passive"))
      (node (ref "R60") (pin "1") (pinfunction "1_1") (pintype "passive"))
      (node (ref "R62") (pin "1") (pinfunction "1_1") (pintype "passive"))
    )
    (net (code "8") (name "GND") (class "Default")
      (node (ref "C60") (pin "2") (pinfunction "2_2") (pintype "passive"))
      (node (ref "C61") (pin "2") (pinfunction "2_2") (pintype "passive"))
      (node (ref "C63") (pin "2") (pinfunction "2_2") (pintype "passive"))
      (node (ref "C91") (pin "2") (pinfunction "2_2") (pintype "passive"))
      (node (ref "C92") (pin "2") (pinfunction "2_2") (pintype "passive"))
      (node (ref "C93") (pin "2") (pinfunction "2_2") (pintype "passive"))
      (node (ref "C94") (pin "2") (pinfunction "2_2") (pintype "passive"))
      (node (ref "C95") (pin "2") (pinfunction "2_2") (pintype "passive"))
      (node (ref "C96") (pin "2") (pinfunction "2_2") (pintype "passive"))
      (node (ref "C97") (pin "2") (pinfunction "2_2") (pintype "passive"))
      (node (ref "C98") (pin "2") (pinfunction "2_2") (pintype "passive"))
      (node (ref "C99") (pin "2") (pinfunction "2_2") (pintype "passive"))
      (node (ref "Q13") (pin "2") (pinfunction "2_2") (pintype "passive"))
      (node (ref "Q14") (pin "2") (pinfunction "2_2") (pintype "passive"))
      (node (ref "Q15") (pin "2") (pinfunction "2_2") (pintype "passive"))
      (node (ref "Q16") (pin "2") (pinfunction "2_2") (pintype "passive"))
      (node (ref "Q17") (pin "2") (pinfunction "2_2") (pintype "passive"))
      (node (ref "Q18") (pin "2") (pinfunction "2_2") (pintype "passive"))
      (node (ref "Q19") (pin "2") (pinfunction "2_2") (pintype "passive"))
      (node (ref "Q20") (pin "2") (pinfunction "2_2") (pintype "passive"))
      (node (ref "Q21") (pin "2") (pinfunction "2_2") (pintype "passive"))
      (node (ref "Q22") (pin "2") (pinfunction "2_2") (pintype "passive"))
      (node (ref "Q23") (pin "2") (pinfunction "2_2") (pintype "passive"))
      (node (ref "Q24") (pin "2") (pinfunction "2_2") (pintype "passive"))
      (node (ref "R112") (pin "1") (pinfunction "1_1") (pintype "passive"))
      (node (ref "R112") (pin "2") (pinfunction "2_2") (pintype "passive"))
      (node (ref "R113") (pin "1") (pinfunction "1_1") (pintype "passive"))
      (node (ref "R113") (pin "2") (pinfunction "2_2") (pintype "passive"))
      (node (ref "R64") (pin "1") (pinfunction "1_1") (pintype "passive"))
      (node (ref "R65") (pin "1") (pinfunction "1_1") (pintype "passive"))
      (node (ref "R66") (pin "1") (pinfunction "1_1") (pintype "passive"))
      (node (ref "R67") (pin "1") (pinfunction "1_1") (pintype "passive"))
      (node (ref "R68") (pin "1") (pinfunction "1_1") (pintype "passive"))
      (node (ref "R69") (pin "1") (pinfunction "1_1") (pintype "passive"))
      (node (ref "R70") (pin "1") (pinfunction "1_1") (pintype "passive"))
      (node (ref "R71") (pin "1") (pinfunction "1_1") (pintype "passive"))
      (node (ref "R85") (pin "1") (pinfunction "1_1") (pintype "passive"))
      (node (ref "R85") (pin "2") (pinfunction "2_2") (pintype "passive"))
      (node (ref "R86") (pin "1") (pinfunction "1_1") (pintype "passive"))
      (node (ref "R86") (pin "2") (pinfunction "2_2") (pintype "passive"))
      (node (ref "R87") (pin "1") (pinfunction "1_1") (pintype "passive"))
      (node (ref "R87") (pin "2") (pinfunction "2_2") (pintype "passive"))
    )
    (net (code "9") (name "Net-(C1-Pad1)") (class "Default")
      (node (ref "C1") (pin "1") (pinfunction "1_1") (pintype "passive"))
      (node (ref "C7") (pin "2") (pinfunction "2_2") (pintype "passive"))
    )
    (net (code "10") (name "Net-(C2-Pad1)") (class "Default")
      (node (ref "C2") (pin "1") (pinfunction "1_1") (pintype "passive"))
      (node (ref "C8") (pin "2") (pinfunction "2_2") (pintype "passive"))
    )
    (net (code "11") (name "Net-(C3-Pad1)") (class "Default")
      (node (ref "C3") (pin "1") (pinfunction "1_1") (pintype "passive"))
      (node (ref "C9") (pin "2") (pinfunction "2_2") (pintype "passive"))
    )
    (net (code "12") (name "Net-(C10-Pad1)") (class "Default")
      (node (ref "C10") (pin "1") (pinfunction "1_1") (pintype "passive"))
      (node (ref "C16") (pin "2") (pinfunction "2_2") (pintype "passive"))
    )
    (net (code "13") (name "Net-(C10-Pad2)") (class "Default")
      (node (ref "C10") (pin "2") (pinfunction "2_2") (pintype "passive"))
      (node (ref "C4") (pin "1") (pinfunction "1_1") (pintype "passive"))
    )
    (net (code "14") (name "Net-(C11-Pad1)") (class "Default")
      (node (ref "C11") (pin "1") (pinfunction "1_1") (pintype "passive"))
      (node (ref "C17") (pin "2") (pinfunction "2_2") (pintype "passive"))
    )
    (net (code "15") (name "Net-(C11-Pad2)") (class "Default")
      (node (ref "C11") (pin "2") (pinfunction "2_2") (pintype "passive"))
      (node (ref "C5") (pin "1") (pinfunction "1_1") (pintype "passive"))
    )
    (net (code "16") (name "Net-(C12-Pad1)") (class "Default")
      (node (ref "C12") (pin "1") (pinfunction "1_1") (pintype "passive"))
      (node (ref "C18") (pin "2") (pinfunction "2_2") (pintype "passive"))
    )
    (net (code "17") (name "Net-(C12-Pad2)") (class "Default")
      (node (ref "C12") (pin "2") (pinfunction "2_2") (pintype "passive"))
      (node (ref "C6") (pin "1") (pinfunction "1_1") (pintype "passive"))
    )
    (net (code "18") (name "Net-(C13-Pad1)") (class "Default")
      (node (ref "C13") (pin "1") (pinfunction "1_1") (pintype "passive"))
      (node (ref "C25") (pin "2") (pinfunction "2_2") (pintype "passive"))
    )
    (net (code "19") (name "Net-(C13-Pad2)") (class "Default")
      (node (ref "C13") (pin "2") (pinfunction "2_2") (pintype "passive"))
      (node (ref "C7") (pin "1") (pinfunction "1_1") (pintype "passive"))
    )
    (net (code "20") (name "Net-(C14-Pad1)") (class "Default")
      (node (ref "C14") (pin "1") (pinfunction "1_1") (pintype "passive"))
      (node (ref "C26") (pin "2") (pinfunction "2_2") (pintype "passive"))
    )
    (net (code "21") (name "Net-(C14-Pad2)") (class "Default")
      (node (ref "C14") (pin "2") (pinfunction "2_2") (pintype "passive"))
      (node (ref "C8") (pin "1") (pinfunction "1_1") (pintype "passive"))
    )
    (net (code "22") (name "Net-(C15-Pad1)") (class "Default")
      (node (ref "C15") (pin "1") (pinfunction "1_1") (pintype "passive"))
      (node (ref "C27") (pin "2") (pinfunction "2_2") (pintype "passive"))
    )
    (net (code "23") (name "Net-(C15-Pad2)") (class "Default")
      (node (ref "C15") (pin "2") (pinfunction "2_2") (pintype "passive"))
      (node (ref "C9") (pin "1") (pinfunction "1_1") (pintype "passive"))
    )
    (net (code "24") (name "Net-(C16-Pad1)") (class "Default")
      (node (ref "C16") (pin "1") (pinfunction "1_1") (pintype "passive"))
      (node (ref "C28") (pin "2") (pinfunction "2_2") (pintype "passive"))
    )
    (net (code "25") (name "Net-(C17-Pad1)") (class "Default")
      (node (ref "C17") (pin "1") (pinfunction "1_1") (pintype "passive"))
      (node (ref "C29") (pin "2") (pinfunction "2_2") (pintype "passive"))
    )
    (net (code "26") (name "Net-(C18-Pad1)") (class "Default")
      (node (ref "C18") (pin "1") (pinfunction "1_1") (pintype "passive"))
      (node (ref "C30") (pin "2") (pinfunction "2_2") (pintype "passive"))
    )
    (net (code "27") (name "Net-(C25-Pad1)") (class "Default")
      (node (ref "C25") (pin "1") (pinfunction "1_1") (pintype "passive"))
      (node (ref "C34") (pin "2") (pinfunction "2_2") (pintype "passive"))
    )
    (net (code "28") (name "Net-(C26-Pad1)") (class "Default")
      (node (ref "C26") (pin "1") (pinfunction "1_1") (pintype "passive"))
      (node (ref "C35") (pin "2") (pinfunction "2_2") (pintype "passive"))
    )
    (net (code "29") (name "Net-(C27-Pad1)") (class "Default")
      (node (ref "C27") (pin "1") (pinfunction "1_1") (pintype "passive"))
      (node (ref "C36") (pin "2") (pinfunction "2_2") (pintype "passive"))
    )
    (net (code "30") (name "Net-(C28-Pad1)") (class "Default")
      (node (ref "C28") (pin "1") (pinfunction "1_1") (pintype "passive"))
      (node (ref "C37") (pin "2") (pinfunction "2_2") (pintype "passive"))
    )
    (net (code "31") (name "Net-(C29-Pad1)") (class "Default")
      (node (ref "C29") (pin "1") (pinfunction "1_1") (pintype "passive"))
      (node (ref "C38") (pin "2") (pinfunction "2_2") (pintype "passive"))
    )
    (net (code "32") (name "Net-(C30-Pad1)") (class "Default")
      (node (ref "C30") (pin "1") (pinfunction "1_1") (pintype "passive"))
      (node (ref "C39") (pin "2") (pinfunction "2_2") (pintype "passive"))
    )
    (net (code "33") (name "Net-(C31-Pad1)") (class "Default")
      (node (ref "C31") (pin "1") (pinfunction "1_1") (pintype "passive"))
      (node (ref "R6") (pin "1") (pinfunction "1_1") (pintype "passive"))
    )
    (net (code "34") (name "Net-(C32-Pad1)") (class "Default")
      (node (ref "C32") (pin "1") (pinfunction "1_1") (pintype "passive"))
      (node (ref "R8") (pin "1") (pinfunction "1_1") (pintype "passive"))
    )
    (net (code "35") (name "Net-(C33-Pad1)") (class "Default")
      (node (ref "C33") (pin "1") (pinfunction "1_1") (pintype "passive"))
      (node (ref "R9") (pin "1") (pinfunction "1_1") (pintype "passive"))
    )
    (net (code "36") (name "Net-(C34-Pad1)") (class "Default")
      (node (ref "C34") (pin "1") (pinfunction "1_1") (pintype "passive"))
      (node (ref "C40") (pin "2") (pinfunction "2_2") (pintype "passive"))
    )
    (net (code "37") (name "Net-(C35-Pad1)") (class "Default")
      (node (ref "C35") (pin "1") (pinfunction "1_1") (pintype "passive"))
      (node (ref "C41") (pin "2") (pinfunction "2_2") (pintype "passive"))
    )
    (net (code "38") (name "Net-(C36-Pad1)") (class "Default")
      (node (ref "C36") (pin "1") (pinfunction "1_1") (pintype "passive"))
      (node (ref "C42") (pin "2") (pinfunction "2_2") (pintype "passive"))
    )
    (net (code "39") (name "Net-(C37-Pad1)") (class "Default")
      (node (ref "C37") (pin "1") (pinfunction "1_1") (pintype "passive"))
      (node (ref "C43") (pin "2") (pinfunction "2_2") (pintype "passive"))
    )
    (net (code "40") (name "Net-(C38-Pad1)") (class "Default")
      (node (ref "C38") (pin "1") (pinfunction "1_1") (pintype "passive"))
      (node (ref "C44") (pin "2") (pinfunction "2_2") (pintype "passive"))
    )
    (net (code "41") (name "Net-(C39-Pad1)") (class "Default")
      (node (ref "C39") (pin "1") (pinfunction "1_1") (pintype "passive"))
      (node (ref "C45") (pin "2") (pinfunction "2_2") (pintype "passive"))
    )
    (net (code "42") (name "Net-(C40-Pad1)") (class "Default")
      (node (ref "C40") (pin "1") (pinfunction "1_1") (pintype "passive"))
      (node (ref "R64") (pin "2") (pinfunction "2_2") (pintype "passive"))
    )
    (net (code "43") (name "Net-(C41-Pad1)") (class "Default")
      (node (ref "C41") (pin "1") (pinfunction "1_1") (pintype "passive"))
      (node (ref "R65") (pin "2") (pinfunction "2_2") (pintype "passive"))
    )
    (net (code "44") (name "Net-(C42-Pad1)") (class "Default")
      (node (ref "C42") (pin "1") (pinfunction "1_1") (pintype "passive"))
      (node (ref "R66") (pin "2") (pinfunction "2_2") (pintype "passive"))
    )
    (net (code "45") (name "Net-(C43-Pad1)") (class "Default")
      (node (ref "C43") (pin "1") (pinfunction "1_1") (pintype "passive"))
      (node (ref "R67") (pin "2") (pinfunction "2_2") (pintype "passive"))
    )
    (net (code "46") (name "Net-(C44-Pad1)") (class "Default")
      (node (ref "C44") (pin "1") (pinfunction "1_1") (pintype "passive"))
      (node (ref "R68") (pin "2") (pinfunction "2_2") (pintype "passive"))
    )
    (net (code "47") (name "Net-(C45-Pad1)") (class "Default")
      (node (ref "C45") (pin "1") (pinfunction "1_1") (pintype "passive"))
      (node (ref "R69") (pin "2") (pinfunction "2_2") (pintype "passive"))
    )
    (net (code "48") (name "Net-(C46-Pad1)") (class "Default")
      (node (ref "C46") (pin "1") (pinfunction "1_1") (pintype "passive"))
      (node (ref "R11") (pin "1") (pinfunction "1_1") (pintype "passive"))
    )
    (net (code "49") (name "Net-(C47-Pad1)") (class "Default")
      (node (ref "C47") (pin "1") (pinfunction "1_1") (pintype "passive"))
      (node (ref "R13") (pin "1") (pinfunction "1_1") (pintype "passive"))
    )
    (net (code "50") (name "Net-(C48-Pad1)") (class "Default")
      (node (ref "C48") (pin "1") (pinfunction "1_1") (pintype "passive"))
      (node (ref "R20") (pin "1") (pinfunction "1_1") (pintype "passive"))
    )
    (net (code "51") (name "Net-(C52-Pad1)") (class "Default")
      (node (ref "C52") (pin "1") (pinfunction "1_1") (pintype "passive"))
      (node (ref "R21") (pin "1") (pinfunction "1_1") (pintype "passive"))
    )
    (net (code "52") (name "Net-(C53-Pad1)") (class "Default")
      (node (ref "C53") (pin "1") (pinfunction "1_1") (pintype "passive"))
      (node (ref "R14") (pin "1") (pinfunction "1_1") (pintype "passive"))
    )
    (net (code "53") (name "Net-(C54-Pad1)") (class "Default")
      (node (ref "C54") (pin "1") (pinfunction "1_1") (pintype "passive"))
      (node (ref "R16") (pin "1") (pinfunction "1_1") (pintype "passive"))
    )
    (net (code "54") (name "Net-(C55-Pad1)") (class "Default")
      (node (ref "C55") (pin "1") (pinfunction "1_1") (pintype "passive"))
      (node (ref "R22") (pin "1") (pinfunction "1_1") (pintype "passive"))
    )
    (net (code "55") (name "Net-(C56-Pad1)") (class "Default")
      (node (ref "C56") (pin "1") (pinfunction "1_1") (pintype "passive"))
      (node (ref "R25") (pin "1") (pinfunction "1_1") (pintype "passive"))
    )
    (net (code "56") (name "Net-(C59-Pad1)") (class "Default")
      (node (ref "C59") (pin "1") (pinfunction "1_1") (pintype "passive"))
      (node (ref "R28") (pin "1") (pinfunction "1_1") (pintype "passive"))
    )
    (net (code "57") (name "Net-(C60-Pad1)") (class "Default")
      (node (ref "C60") (pin "1") (pinfunction "1_1") (pintype "passive"))
      (node (ref "R41") (pin "1") (pinfunction "1_1") (pintype "passive"))
    )
    (net (code "58") (name "Net-(C61-Pad1)") (class "Default")
      (node (ref "C61") (pin "1") (pinfunction "1_1") (pintype "passive"))
      (node (ref "R43") (pin "1") (pinfunction "1_1") (pintype "passive"))
    )
    (net (code "59") (name "Net-(C63-Pad1)") (class "Default")
      (node (ref "C63") (pin "1") (pinfunction "1_1") (pintype "passive"))
      (node (ref "R45") (pin "1") (pinfunction "1_1") (pintype "passive"))
    )
    (net (code "60") (name "Net-(C91-Pad1)") (class "Default")
      (node (ref "C91") (pin "1") (pinfunction "1_1") (pintype "passive"))
      (node (ref "R49") (pin "1") (pinfunction "1_1") (pintype "passive"))
    )
    (net (code "61") (name "Net-(C92-Pad1)") (class "Default")
      (node (ref "C92") (pin "1") (pinfunction "1_1") (pintype "passive"))
      (node (ref "R51") (pin "1") (pinfunction "1_1") (pintype "passive"))
    )
    (net (code "62") (name "Net-(C93-Pad1)") (class "Default")
      (node (ref "C93") (pin "1") (pinfunction "1_1") (pintype "passive"))
      (node (ref "R53") (pin "1") (pinfunction "1_1") (pintype "passive"))
    )
    (net (code "63") (name "Net-(C94-Pad1)") (class "Default")
      (node (ref "C94") (pin "1") (pinfunction "1_1") (pintype "passive"))
      (node (ref "R55") (pin "1") (pinfunction "1_1") (pintype "passive"))
    )
    (net (code "64") (name "Net-(C95-Pad1)") (class "Default")
      (node (ref "C95") (pin "1") (pinfunction "1_1") (pintype "passive"))
      (node (ref "R57") (pin "1") (pinfunction "1_1") (pintype "passive"))
    )
    (net (code "65") (name "Net-(C96-Pad1)") (class "Default")
      (node (ref "C96") (pin "1") (pinfunction "1_1") (pintype "passive"))
      (node (ref "R59") (pin "1") (pinfunction "1_1") (pintype "passive"))
    )
    (net (code "66") (name "Net-(C97-Pad1)") (class "Default")
      (node (ref "C97") (pin "1") (pinfunction "1_1") (pintype "passive"))
      (node (ref "R61") (pin "1") (pinfunction "1_1") (pintype "passive"))
    )
    (net (code "67") (name "Net-(C98-Pad1)") (class "Default")
      (node (ref "C98") (pin "1") (pinfunction "1_1") (pintype "passive"))
      (node (ref "R63") (pin "1") (pinfunction "1_1") (pintype "passive"))
    )
    (net (code "68") (name "Net-(C99-Pad1)") (class "Default")
      (node (ref "C99") (pin "1") (pinfunction "1_1") (pintype "passive"))
      (node (ref "R47") (pin "1") (pinfunction "1_1") (pintype "passive"))
    )
    (net (code "69") (name "Net-(D9-A)") (class "Default")
      (node (ref "D9") (pin "1") (pinfunction "A_1") (pintype "passive"))
      (node (ref "R90") (pin "1") (pinfunction "1_1") (pintype "passive"))
    )
    (net (code "70") (name "Net-(D10-A)") (class "Default")
      (node (ref "D10") (pin "1") (pinfunction "A_1") (pintype "passive"))
      (node (ref "R89") (pin "1") (pinfunction "1_1") (pintype "passive"))
    )
    (net (code "71") (name "Net-(D11-A)") (class "Default")
      (node (ref "D11") (pin "1") (pinfunction "A_1") (pintype "passive"))
      (node (ref "R88") (pin "1") (pinfunction "1_1") (pintype "passive"))
    )
    (net (code "72") (name "Net-(D12-A)") (class "Default")
      (node (ref "D12") (pin "1") (pinfunction "A_1") (pintype "passive"))
      (node (ref "R91") (pin "1") (pinfunction "1_1") (pintype "passive"))
    )
    (net (code "73") (name "Net-(D13-A)") (class "Default")
      (node (ref "D13") (pin "1") (pinfunction "A_1") (pintype "passive"))
      (node (ref "R92") (pin "1") (pinfunction "1_1") (pintype "passive"))
    )
    (net (code "74") (name "Net-(D14-A)") (class "Default")
      (node (ref "D14") (pin "1") (pinfunction "A_1") (pintype "passive"))
      (node (ref "R93") (pin "1") (pinfunction "1_1") (pintype "passive"))
    )
    (net (code "75") (name "Net-(D15-A)") (class "Default")
      (node (ref "D15") (pin "1") (pinfunction "A_1") (pintype "passive"))
      (node (ref "R94") (pin "1") (pinfunction "1_1") (pintype "passive"))
    )
    (net (code "76") (name "Net-(D16-A)") (class "Default")
      (node (ref "D16") (pin "1") (pinfunction "A_1") (pintype "passive"))
      (node (ref "R95") (pin "1") (pinfunction "1_1") (pintype "passive"))
    )
    (net (code "77") (name "Net-(D17-A)") (class "Default")
      (node (ref "D17") (pin "1") (pinfunction "A_1") (pintype "passive"))
      (node (ref "R96") (pin "1") (pinfunction "1_1") (pintype "passive"))
    )
    (net (code "78") (name "Net-(D18-A)") (class "Default")
      (node (ref "D18") (pin "1") (pinfunction "A_1") (pintype "passive"))
      (node (ref "R97") (pin "1") (pinfunction "1_1") (pintype "passive"))
    )
    (net (code "79") (name "Net-(D19-A)") (class "Default")
      (node (ref "D19") (pin "1") (pinfunction "A_1") (pintype "passive"))
      (node (ref "R98") (pin "1") (pinfunction "1_1") (pintype "passive"))
    )
    (net (code "80") (name "Net-(D20-A)") (class "Default")
      (node (ref "D20") (pin "1") (pinfunction "A_1") (pintype "passive"))
      (node (ref "R99") (pin "1") (pinfunction "1_1") (pintype "passive"))
    )
    (net (code "81") (name "Net-(D21-A)") (class "Default")
      (node (ref "D21") (pin "1") (pinfunction "A_1") (pintype "passive"))
      (node (ref "R100") (pin "1") (pinfunction "1_1") (pintype "passive"))
    )
    (net (code "82") (name "Net-(D22-A)") (class "Default")
      (node (ref "D22") (pin "1") (pinfunction "A_1") (pintype "passive"))
      (node (ref "R104") (pin "1") (pinfunction "1_1") (pintype "passive"))
    )
    (net (code "83") (name "Net-(D23-A)") (class "Default")
      (node (ref "D23") (pin "1") (pinfunction "A_1") (pintype "passive"))
      (node (ref "R105") (pin "1") (pinfunction "1_1") (pintype "passive"))
    )
    (net (code "84") (name "Net-(D24-A)") (class "Default")
      (node (ref "D24") (pin "1") (pinfunction "A_1") (pintype "passive"))
      (node (ref "R106") (pin "1") (pinfunction "1_1") (pintype "passive"))
    )
    (net (code "85") (name "Net-(D25-A)") (class "Default")
      (node (ref "D25") (pin "1") (pinfunction "A_1") (pintype "passive"))
      (node (ref "R107") (pin "1") (pinfunction "1_1") (pintype "passive"))
    )
    (net (code "86") (name "Net-(D26-A)") (class "Default")
      (node (ref "D26") (pin "1") (pinfunction "A_1") (pintype "passive"))
      (node (ref "R108") (pin "1") (pinfunction "1_1") (pintype "passive"))
    )
    (net (code "87") (name "Net-(D27-A)") (class "Default")
      (node (ref "D27") (pin "1") (pinfunction "A_1") (pintype "passive"))
      (node (ref "R109") (pin "1") (pinfunction "1_1") (pintype "passive"))
    )
    (net (code "88") (name "Net-(D28-A)") (class "Default")
      (node (ref "D28") (pin "1") (pinfunction "A_1") (pintype "passive"))
      (node (ref "R110") (pin "1") (pinfunction "1_1") (pintype "passive"))
    )
    (net (code "89") (name "Net-(D29-A)") (class "Default")
      (node (ref "D29") (pin "1") (pinfunction "A_1") (pintype "passive"))
      (node (ref "R111") (pin "1") (pinfunction "1_1") (pintype "passive"))
    )
    (net (code "90") (name "Net-(D30-A)") (class "Default")
      (node (ref "D30") (pin "1") (pinfunction "A_1") (pintype "passive"))
      (node (ref "R101") (pin "1") (pinfunction "1_1") (pintype "passive"))
    )
    (net (code "91") (name "Net-(D31-A)") (class "Default")
      (node (ref "D31") (pin "1") (pinfunction "A_1") (pintype "passive"))
      (node (ref "R102") (pin "1") (pinfunction "1_1") (pintype "passive"))
    )
    (net (code "92") (name "Net-(D32-A)") (class "Default")
      (node (ref "D32") (pin "1") (pinfunction "A_1") (pintype "passive"))
      (node (ref "R103") (pin "1") (pinfunction "1_1") (pintype "passive"))
    )
    (net (code "93") (name "Net-(Q1-Pad1)") (class "Default")
      (node (ref "Q1") (pin "1") (pinfunction "1_1") (pintype "passive"))
      (node (ref "R4") (pin "2") (pinfunction "2_2") (pintype "passive"))
      (node (ref "R6") (pin "2") (pinfunction "2_2") (pintype "passive"))
      (node (ref "R90") (pin "2") (pinfunction "2_2") (pintype "passive"))
    )
    (net (code "94") (name "Net-(Q2-Pad1)") (class "Default")
      (node (ref "Q2") (pin "1") (pinfunction "1_1") (pintype "passive"))
      (node (ref "R5") (pin "2") (pinfunction "2_2") (pintype "passive"))
      (node (ref "R8") (pin "2") (pinfunction "2_2") (pintype "passive"))
      (node (ref "R89") (pin "2") (pinfunction "2_2") (pintype "passive"))
    )
    (net (code "95") (name "Net-(Q3-Pad1)") (class "Default")
      (node (ref "Q3") (pin "1") (pinfunction "1_1") (pintype "passive"))
      (node (ref "R7") (pin "2") (pinfunction "2_2") (pintype "passive"))
      (node (ref "R88") (pin "2") (pinfunction "2_2") (pintype "passive"))
      (node (ref "R9") (pin "2") (pinfunction "2_2") (pintype "passive"))
    )
    (net (code "96") (name "Net-(Q4-Pad1)") (class "Default")
      (node (ref "Q4") (pin "1") (pinfunction "1_1") (pintype "passive"))
      (node (ref "R10") (pin "2") (pinfunction "2_2") (pintype "passive"))
      (node (ref "R11") (pin "2") (pinfunction "2_2") (pintype "passive"))
      (node (ref "R91") (pin "2") (pinfunction "2_2") (pintype "passive"))
    )
    (net (code "97") (name "Net-(Q5-Pad1)") (class "Default")
      (node (ref "Q5") (pin "1") (pinfunction "1_1") (pintype "passive"))
      (node (ref "R12") (pin "2") (pinfunction "2_2") (pintype "passive"))
      (node (ref "R13") (pin "2") (pinfunction "2_2") (pintype "passive"))
      (node (ref "R92") (pin "2") (pinfunction "2_2") (pintype "passive"))
    )
    (net (code "98") (name "Net-(Q6-Pad1)") (class "Default")
      (node (ref "Q6") (pin "1") (pinfunction "1_1") (pintype "passive"))
      (node (ref "R14") (pin "2") (pinfunction "2_2") (pintype "passive"))
      (node (ref "R15") (pin "2") (pinfunction "2_2") (pintype "passive"))
      (node (ref "R93") (pin "2") (pinfunction "2_2") (pintype "passive"))
    )
    (net (code "99") (name "Net-(Q7-Pad1)") (class "Default")
      (node (ref "Q7") (pin "1") (pinfunction "1_1") (pintype "passive"))
      (node (ref "R16") (pin "2") (pinfunction "2_2") (pintype "passive"))
      (node (ref "R17") (pin "2") (pinfunction "2_2") (pintype "passive"))
      (node (ref "R94") (pin "2") (pinfunction "2_2") (pintype "passive"))
    )
    (net (code "100") (name "Net-(Q8-Pad1)") (class "Default")
      (node (ref "Q8") (pin "1") (pinfunction "1_1") (pintype "passive"))
      (node (ref "R19") (pin "2") (pinfunction "2_2") (pintype "passive"))
      (node (ref "R20") (pin "2") (pinfunction "2_2") (pintype "passive"))
      (node (ref "R95") (pin "2") (pinfunction "2_2") (pintype "passive"))
    )
    (net (code "101") (name "Net-(Q9-Pad1)") (class "Default")
      (node (ref "Q9") (pin "1") (pinfunction "1_1") (pintype "passive"))
      (node (ref "R21") (pin "2") (pinfunction "2_2") (pintype "passive"))
      (node (ref "R23") (pin "2") (pinfunction "2_2") (pintype "passive"))
      (node (ref "R99") (pin "2") (pinfunction "2_2") (pintype "passive"))
    )
    (net (code "102") (name "Net-(Q10-Pad1)") (class "Default")
      (node (ref "Q10") (pin "1") (pinfunction "1_1") (pintype "passive"))
      (node (ref "R22") (pin "2") (pinfunction "2_2") (pintype "passive"))
      (node (ref "R24") (pin "2") (pinfunction "2_2") (pintype "passive"))
      (node (ref "R96") (pin "2") (pinfunction "2_2") (pintype "passive"))
    )
    (net (code "103") (name "Net-(Q11-Pad1)") (class "Default")
      (node (ref "Q11") (pin "1") (pinfunction "1_1") (pintype "passive"))
      (node (ref "R25") (pin "2") (pinfunction "2_2") (pintype "passive"))
      (node (ref "R26") (pin "2") (pinfunction "2_2") (pintype "passive"))
      (node (ref "R97") (pin "2") (pinfunction "2_2") (pintype "passive"))
    )
    (net (code "104") (name "Net-(Q12-Pad1)") (class "Default")
      (node (ref "Q12") (pin "1") (pinfunction "1_1") (pintype "passive"))
      (node (ref "R27") (pin "2") (pinfunction "2_2") (pintype "passive"))
      (node (ref "R28") (pin "2") (pinfunction "2_2") (pintype "passive"))
      (node (ref "R98") (pin "2") (pinfunction "2_2") (pintype "passive"))
    )
    (net (code "105") (name "Net-(Q13-Pad1)") (class "Default")
      (node (ref "Q13") (pin "1") (pinfunction "1_1") (pintype "passive"))
      (node (ref "R100") (pin "2") (pinfunction "2_2") (pintype "passive"))
      (node (ref "R40") (pin "2") (pinfunction "2_2") (pintype "passive"))
      (node (ref "R41") (pin "2") (pinfunction "2_2") (pintype "passive"))
    )
    (net (code "106") (name "Net-(Q14-Pad1)") (class "Default")
      (node (ref "Q14") (pin "1") (pinfunction "1_1") (pintype "passive"))
      (node (ref "R104") (pin "2") (pinfunction "2_2") (pintype "passive"))
      (node (ref "R42") (pin "2") (pinfunction "2_2") (pintype "passive"))
      (node (ref "R43") (pin "2") (pinfunction "2_2") (pintype "passive"))
    )
    (net (code "107") (name "Net-(Q15-Pad1)") (class "Default")
      (node (ref "Q15") (pin "1") (pinfunction "1_1") (pintype "passive"))
      (node (ref "R105") (pin "2") (pinfunction "2_2") (pintype "passive"))
      (node (ref "R44") (pin "2") (pinfunction "2_2") (pintype "passive"))
      (node (ref "R45") (pin "2") (pinfunction "2_2") (pintype "passive"))
    )
    (net (code "108") (name "Net-(Q16-Pad1)") (class "Default")
      (node (ref "Q16") (pin "1") (pinfunction "1_1") (pintype "passive"))
      (node (ref "R106") (pin "2") (pinfunction "2_2") (pintype "passive"))
      (node (ref "R46") (pin "2") (pinfunction "2_2") (pintype "passive"))
      (node (ref "R47") (pin "2") (pinfunction "2_2") (pintype "passive"))
    )
    (net (code "109") (name "Net-(Q17-Pad1)") (class "Default")
      (node (ref "Q17") (pin "1") (pinfunction "1_1") (pintype "passive"))
      (node (ref "R107") (pin "2") (pinfunction "2_2") (pintype "passive"))
      (node (ref "R48") (pin "2") (pinfunction "2_2") (pintype "passive"))
      (node (ref "R49") (pin "2") (pinfunction "2_2") (pintype "passive"))
    )
    (net (code "110") (name "Net-(Q18-Pad1)") (class "Default")
      (node (ref "Q18") (pin "1") (pinfunction "1_1") (pintype "passive"))
      (node (ref "R110") (pin "2") (pinfunction "2_2") (pintype "passive"))
      (node (ref "R50") (pin "2") (pinfunction "2_2") (pintype "passive"))
      (node (ref "R51") (pin "2") (pinfunction "2_2") (pintype "passive"))
    )
    (net (code "111") (name "Net-(Q19-Pad1)") (class "Default")
      (node (ref "Q19") (pin "1") (pinfunction "1_1") (pintype "passive"))
      (node (ref "R111") (pin "2") (pinfunction "2_2") (pintype "passive"))
      (node (ref "R52") (pin "2") (pinfunction "2_2") (pintype "passive"))
      (node (ref "R53") (pin "2") (pinfunction "2_2") (pintype "passive"))
    )
    (net (code "112") (name "Net-(Q20-Pad1)") (class "Default")
      (node (ref "Q20") (pin "1") (pinfunction "1_1") (pintype "passive"))
      (node (ref "R108") (pin "2") (pinfunction "2_2") (pintype "passive"))
      (node (ref "R54") (pin "2") (pinfunction "2_2") (pintype "passive"))
      (node (ref "R55") (pin "2") (pinfunction "2_2") (pintype "passive"))
    )
    (net (code "113") (name "Net-(Q21-Pad1)") (class "Default")
      (node (ref "Q21") (pin "1") (pinfunction "1_1") (pintype "passive"))
      (node (ref "R101") (pin "2") (pinfunction "2_2") (pintype "passive"))
      (node (ref "R56") (pin "2") (pinfunction "2_2") (pintype "passive"))
      (node (ref "R57") (pin "2") (pinfunction "2_2") (pintype "passive"))
    )
    (net (code "114") (name "Net-(Q22-Pad1)") (class "Default")
      (node (ref "Q22") (pin "1") (pinfunction "1_1") (pintype "passive"))
      (node (ref "R102") (pin "2") (pinfunction "2_2") (pintype "passive"))
      (node (ref "R58") (pin "2") (pinfunction "2_2") (pintype "passive"))
      (node (ref "R59") (pin "2") (pinfunction "2_2") (pintype "passive"))
    )
    (net (code "115") (name "Net-(Q23-Pad1)") (class "Default")
      (node (ref "Q23") (pin "1") (pinfunction "1_1") (pintype "passive"))
      (node (ref "R103") (pin "2") (pinfunction "2_2") (pintype "passive"))
      (node (ref "R60") (pin "2") (pinfunction "2_2") (pintype "passive"))
      (node (ref "R61") (pin "2") (pinfunction "2_2") (pintype "passive"))
    )
    (net (code "116") (name "Net-(Q24-Pad1)") (class "Default")
      (node (ref "Q24") (pin "1") (pinfunction "1_1") (pintype "passive"))
      (node (ref "R109") (pin "2") (pinfunction "2_2") (pintype "passive"))
      (node (ref "R62") (pin "2") (pinfunction "2_2") (pintype "passive"))
      (node (ref "R63") (pin "2") (pinfunction "2_2") (pintype "passive"))
    )
    (net (code "117") (name "Net-(R2-Pad1)") (class "Default")
      (node (ref "R2") (pin "1") (pinfunction "1_1") (pintype "passive"))
      (node (ref "R29") (pin "2") (pinfunction "2_2") (pintype "passive"))
    )
    (net (code "118") (name "Net-(R3-Pad1)") (class "Default")
      (node (ref "R3") (pin "1") (pinfunction "1_1") (pintype "passive"))
      (node (ref "R30") (pin "2") (pinfunction "2_2") (pintype "passive"))
    )
    (net (code "119") (name "Net-(R29-Pad1)") (class "Default")
      (node (ref "R29") (pin "1") (pinfunction "1_1") (pintype "passive"))
      (node (ref "R32") (pin "2") (pinfunction "2_2") (pintype "passive"))
    )
    (net (code "120") (name "Net-(R30-Pad1)") (class "Default")
      (node (ref "R30") (pin "1") (pinfunction "1_1") (pintype "passive"))
      (node (ref "R33") (pin "2") (pinfunction "2_2") (pintype "passive"))
    )
    (net (code "121") (name "Net-(R32-Pad1)") (class "Default")
      (node (ref "R32") (pin "1") (pinfunction "1_1") (pintype "passive"))
      (node (ref "R36") (pin "2") (pinfunction "2_2") (pintype "passive"))
    )
    (net (code "122") (name "Net-(R33-Pad1)") (class "Default")
      (node (ref "R33") (pin "1") (pinfunction "1_1") (pintype "passive"))
      (node (ref "R37") (pin "2") (pinfunction "2_2") (pintype "passive"))
    )
    (net (code "123") (name "Net-(R36-Pad1)") (class "Default")
      (node (ref "R36") (pin "1") (pinfunction "1_1") (pintype "passive"))
      (node (ref "R70") (pin "2") (pinfunction "2_2") (pintype "passive"))
    )
    (net (code "124") (name "Net-(R37-Pad1)") (class "Default")
      (node (ref "R37") (pin "1") (pinfunction "1_1") (pintype "passive"))
      (node (ref "R71") (pin "2") (pinfunction "2_2") (pintype "passive"))
    )
    (net (code "125") (name "Source_1") (class "Default")
      (node (ref "C31") (pin "2") (pinfunction "2_2") (pintype "passive"))
      (node (ref "C32") (pin "2") (pinfunction "2_2") (pintype "passive"))
      (node (ref "C33") (pin "2") (pinfunction "2_2") (pintype "passive"))
      (node (ref "C46") (pin "2") (pinfunction "2_2") (pintype "passive"))
      (node (ref "Q1") (pin "2") (pinfunction "2_2") (pintype "passive"))
      (node (ref "Q13") (pin "3") (pinfunction "3_3") (pintype "passive"))
      (node (ref "Q14") (pin "3") (pinfunction "3_3") (pintype "passive"))
      (node (ref "Q15") (pin "3") (pinfunction "3_3") (pintype "passive"))
      (node (ref "Q16") (pin "3") (pinfunction "3_3") (pintype "passive"))
      (node (ref "Q2") (pin "2") (pinfunction "2_2") (pintype "passive"))
      (node (ref "Q3") (pin "2") (pinfunction "2_2") (pintype "passive"))
      (node (ref "Q4") (pin "2") (pinfunction "2_2") (pintype "passive"))
    )
    (net (code "126") (name "Source_2") (class "Default")
      (node (ref "C47") (pin "2") (pinfunction "2_2") (pintype "passive"))
      (node (ref "C48") (pin "2") (pinfunction "2_2") (pintype "passive"))
      (node (ref "C53") (pin "2") (pinfunction "2_2") (pintype "passive"))
      (node (ref "C54") (pin "2") (pinfunction "2_2") (pintype "passive"))
      (node (ref "Q17") (pin "3") (pinfunction "3_3") (pintype "passive"))
      (node (ref "Q18") (pin "3") (pinfunction "3_3") (pintype "passive"))
      (node (ref "Q19") (pin "3") (pinfunction "3_3") (pintype "passive"))
      (node (ref "Q20") (pin "3") (pinfunction "3_3") (pintype "passive"))
      (node (ref "Q5") (pin "2") (pinfunction "2_2") (pintype "passive"))
      (node (ref "Q6") (pin "2") (pinfunction "2_2") (pintype "passive"))
      (node (ref "Q7") (pin "2") (pinfunction "2_2") (pintype "passive"))
      (node (ref "Q8") (pin "2") (pinfunction "2_2") (pintype "passive"))
    )
    (net (code "127") (name "Source_3") (class "Default")
      (node (ref "C52") (pin "2") (pinfunction "2_2") (pintype "passive"))
      (node (ref "C55") (pin "2") (pinfunction "2_2") (pintype "passive"))
      (node (ref "C56") (pin "2") (pinfunction "2_2") (pintype "passive"))
      (node (ref "C59") (pin "2") (pinfunction "2_2") (pintype "passive"))
      (node (ref "Q10") (pin "2") (pinfunction "2_2") (pintype "passive"))
      (node (ref "Q11") (pin "2") (pinfunction "2_2") (pintype "passive"))
      (node (ref "Q12") (pin "2") (pinfunction "2_2") (pintype "passive"))
      (node (ref "Q21") (pin "3") (pinfunction "3_3") (pintype "passive"))
      (node (ref "Q22") (pin "3") (pinfunction "3_3") (pintype "passive"))
      (node (ref "Q23") (pin "3") (pinfunction "3_3") (pintype "passive"))
      (node (ref "Q24") (pin "3") (pinfunction "3_3") (pintype "passive"))
      (node (ref "Q9") (pin "2") (pinfunction "2_2") (pintype "passive"))
    )
  )
)
